# Elec_2013_Combined.net
KiCad netlist of a schematic drawn in EAGLE
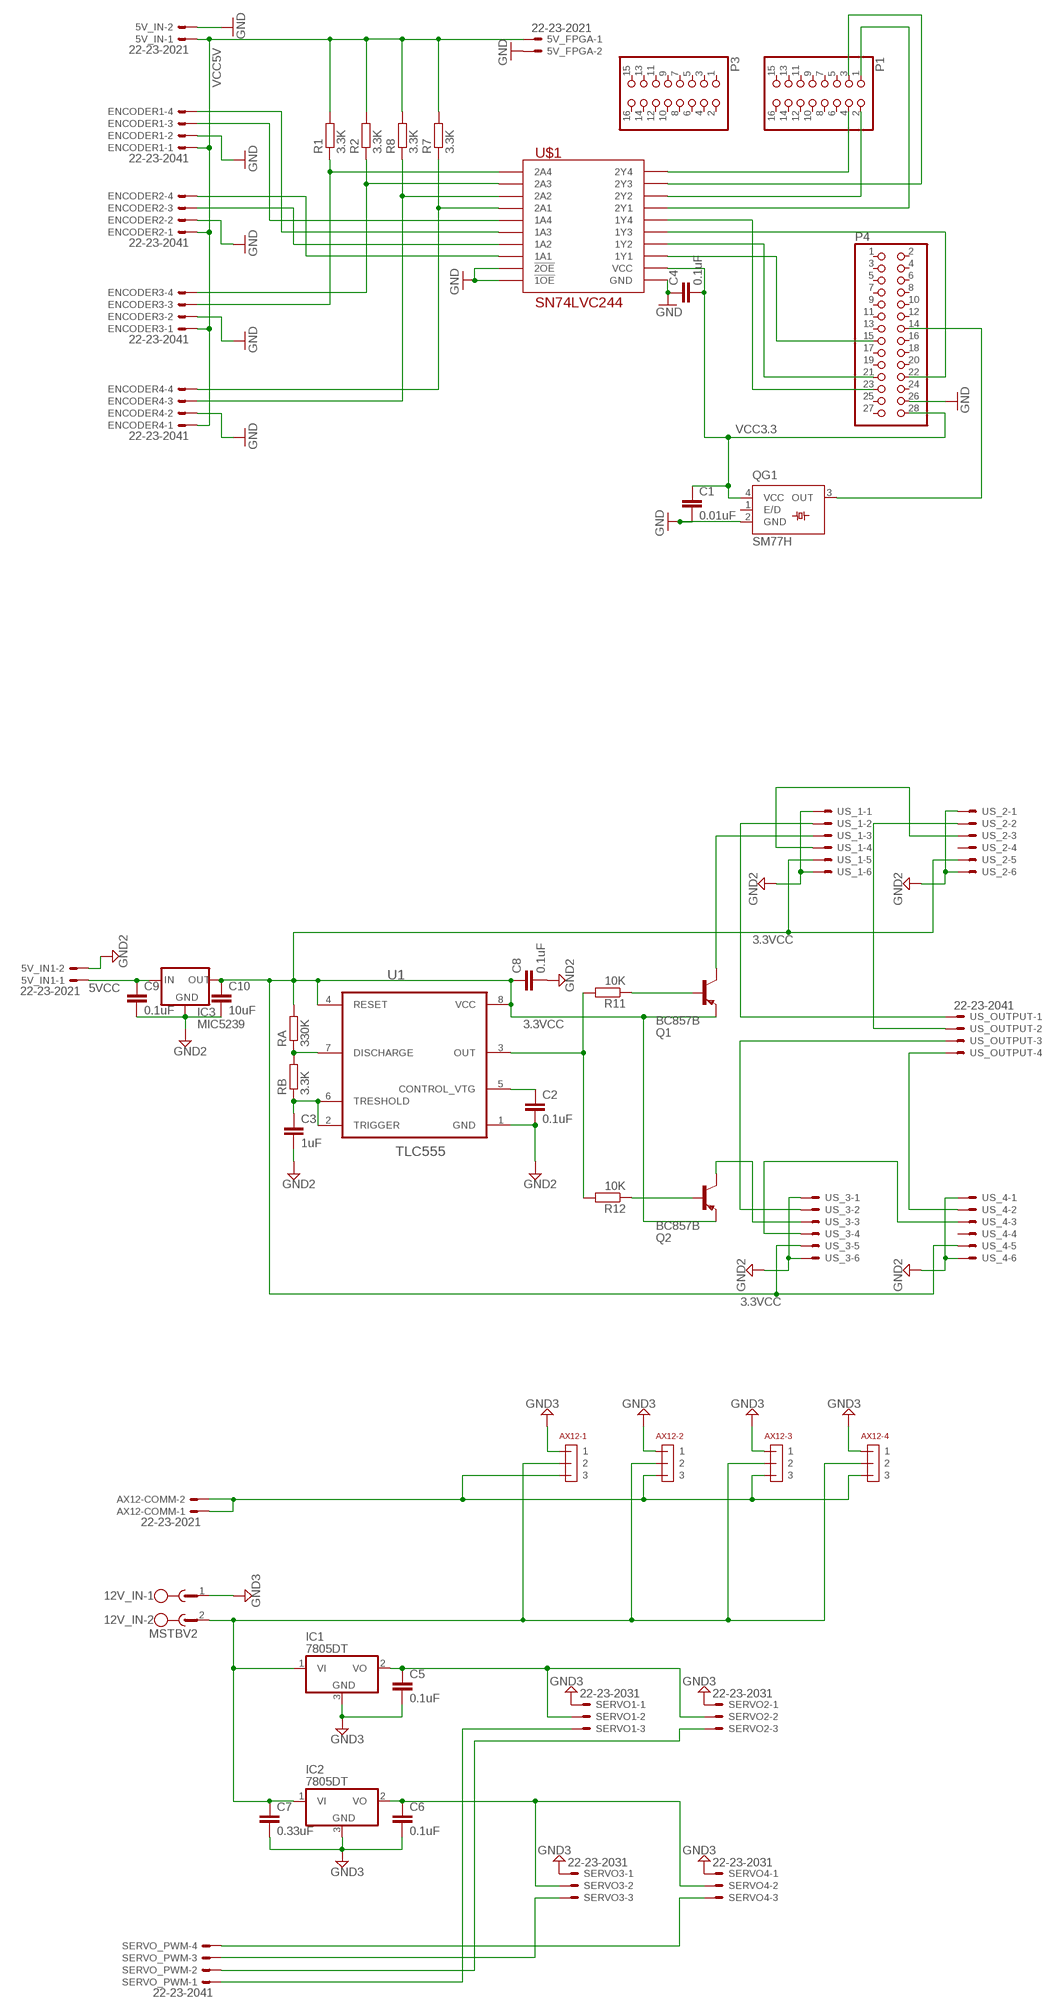
[diagram p0: schematic, sheet 1, part 1 of 2]
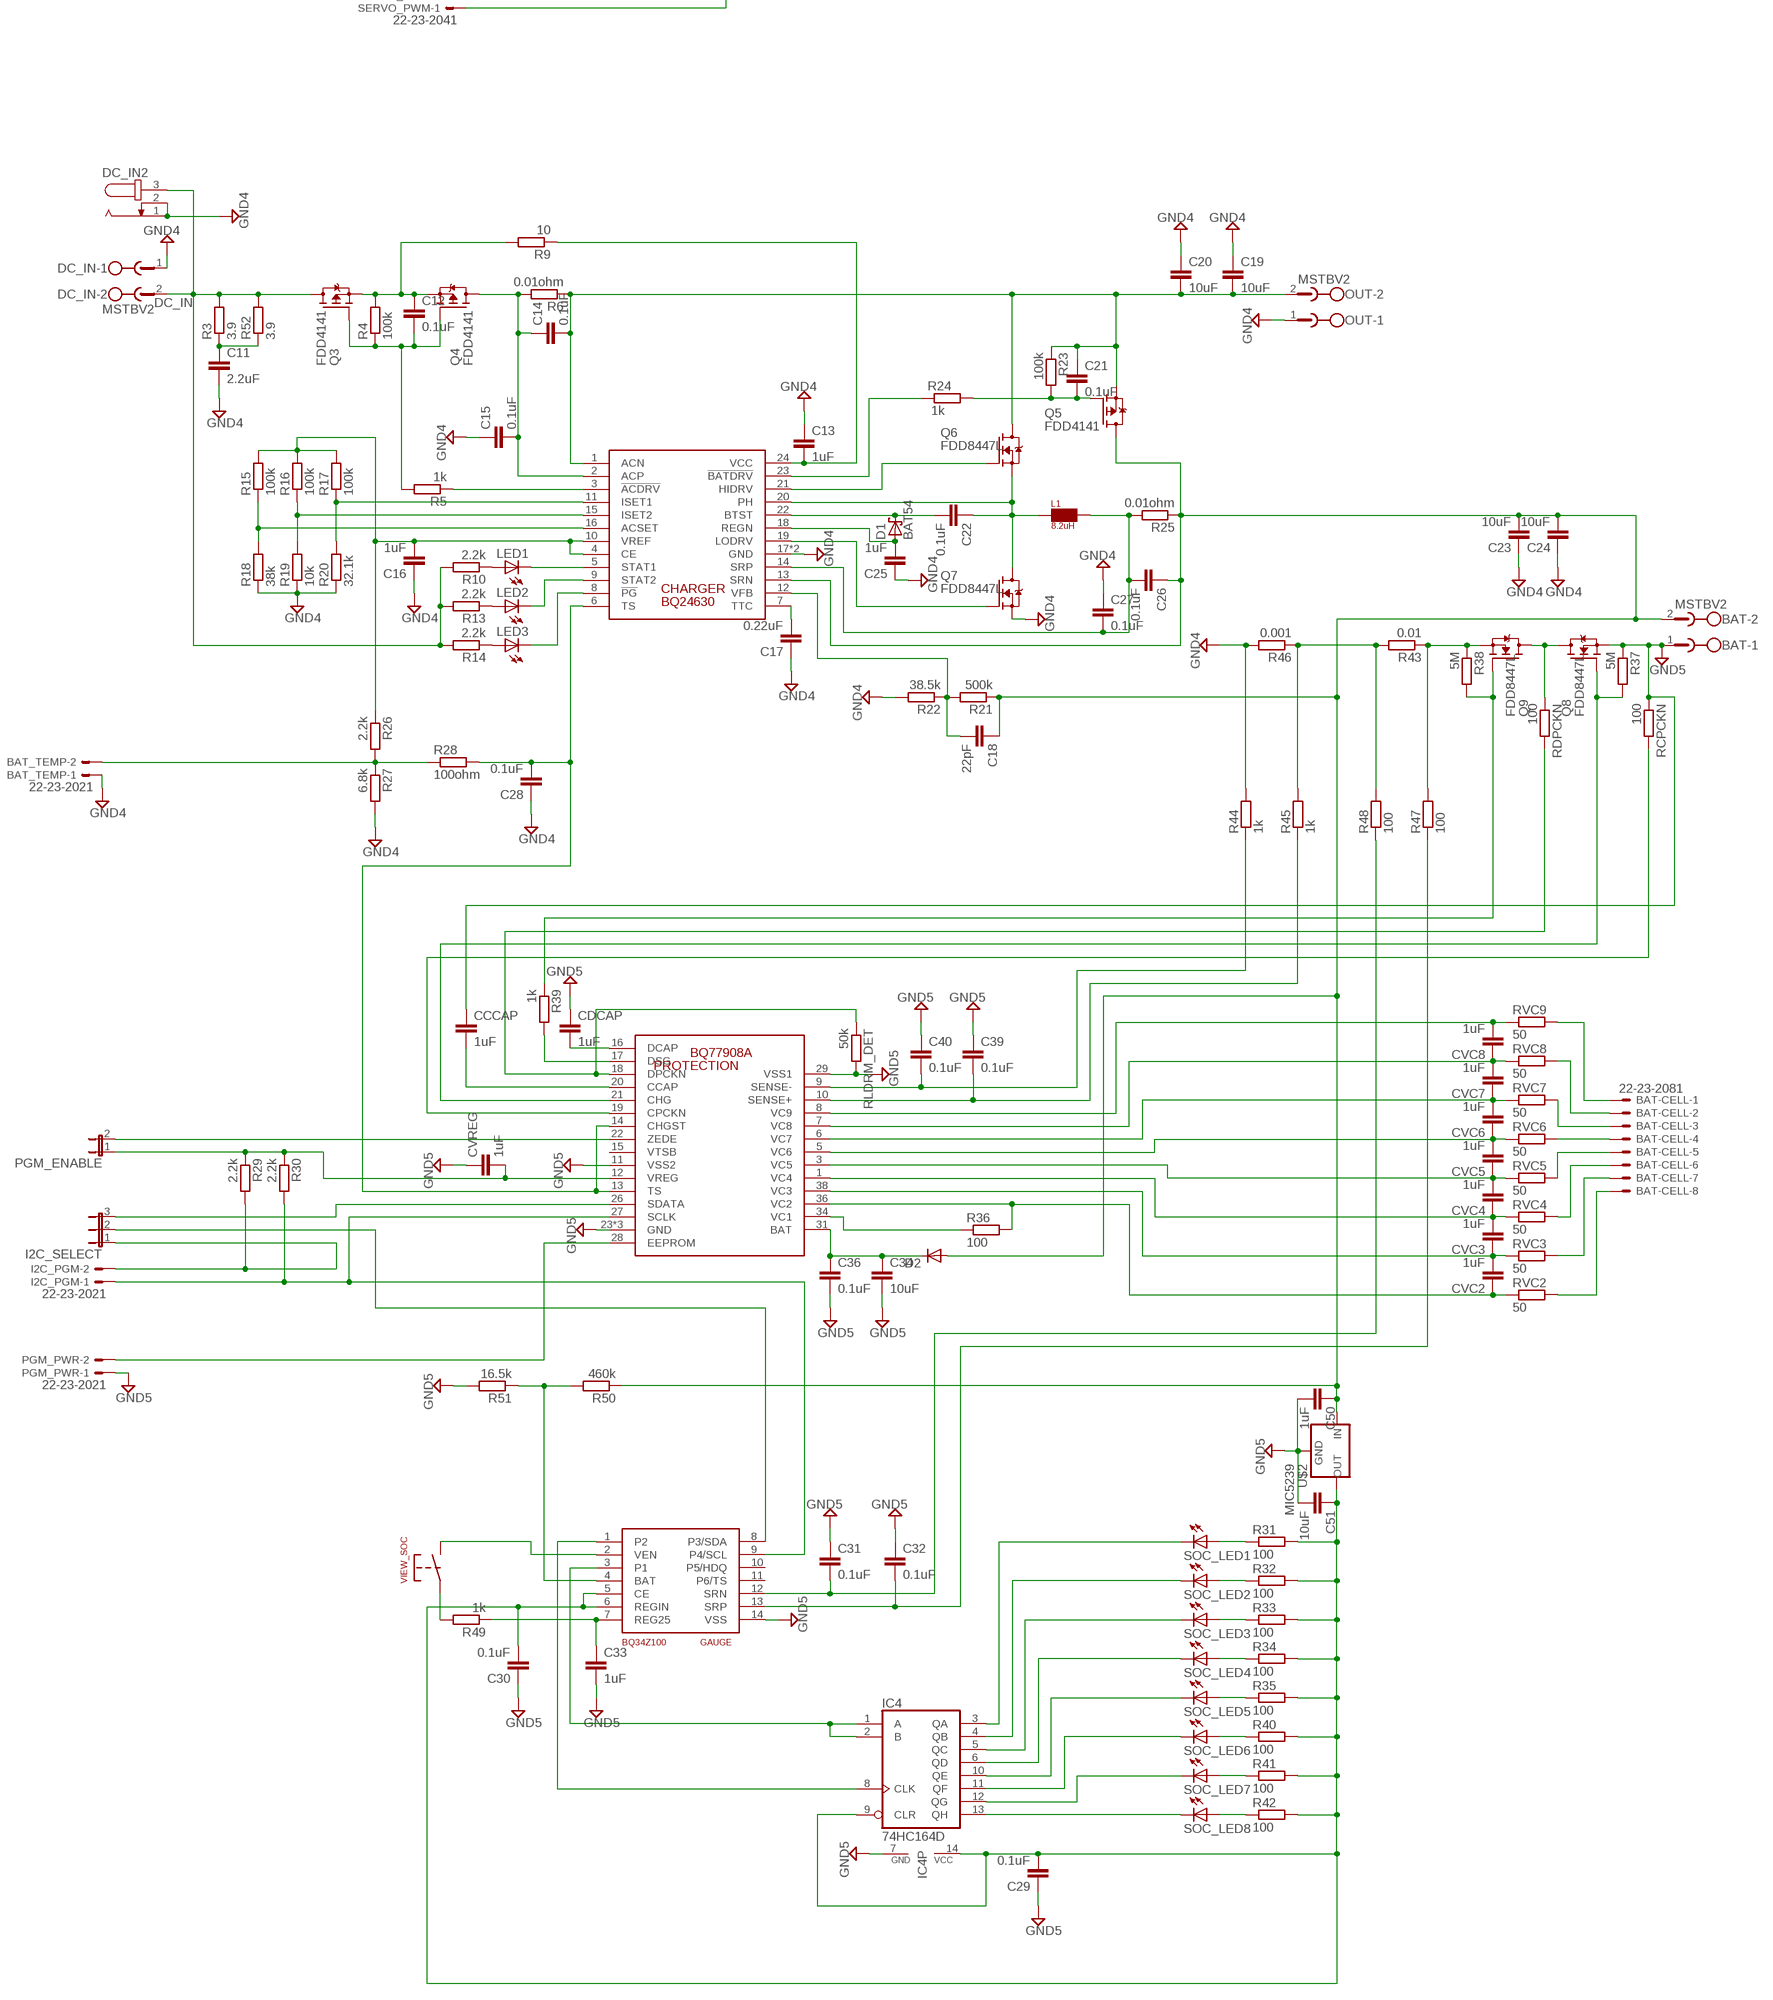
[diagram p1: schematic, sheet 1, part 2 of 2]

(export (version "E")
  (design (tool "Eeschema 10.0.6"))
  (components
    (comp (ref "5V_FPGA")
      (value "22-23-2021")
      (footprint "eagle-import:22-23-2021")
      (fields
        (field (name "MF") "MOLEX")
        (field (name "MF_1") "MOLEX")
        (field (name "MPN") "22-23-2021")
        (field (name "OC_FARNELL") "1462926")
        (field (name "OC_NEWARK") "25C3832")
      )
      (libsource (lib "eagle-import") (part "22-23-2021"))
    )
    (comp (ref "5V_IN")
      (value "22-23-2021")
      (footprint "eagle-import:22-23-2021")
      (fields (field (name "MF") "MOLEX"))
      (libsource (lib "eagle-import") (part "22-23-2021"))
    )
    (comp (ref "5V_IN1")
      (value "22-23-2021")
      (footprint "eagle-import:22-23-2021")
      (fields
        (field (name "MF") "MOLEX")
        (field (name "MF_1") "MOLEX")
        (field (name "MPN") "22-23-2021")
        (field (name "OC_FARNELL") "1462926")
        (field (name "OC_NEWARK") "25C3832")
      )
      (libsource (lib "eagle-import") (part "22-23-2021"))
    )
    (comp (ref "12V_IN")
      (value "MSTBV2")
      (footprint "eagle-import:MSTBV2")
      (fields (field (name "MPN") "MSTBV 2,5/2-GF-5.08"))
      (libsource (lib "eagle-import") (part "MSTBV2"))
    )
    (comp (ref "AX12-1")
      (value "22-03-5035")
      (footprint "eagle-import:22-03-5035")
      (libsource (lib "eagle-import") (part "22-03-5035"))
    )
    (comp (ref "AX12-2")
      (value "22-03-5035")
      (footprint "eagle-import:22-03-5035")
      (libsource (lib "eagle-import") (part "22-03-5035"))
    )
    (comp (ref "AX12-3")
      (value "22-03-5035")
      (footprint "eagle-import:22-03-5035")
      (libsource (lib "eagle-import") (part "22-03-5035"))
    )
    (comp (ref "AX12-4")
      (value "22-03-5035")
      (footprint "eagle-import:22-03-5035")
      (libsource (lib "eagle-import") (part "22-03-5035"))
    )
    (comp (ref "AX12-COMM")
      (value "22-23-2021")
      (footprint "eagle-import:22-23-2021")
      (fields (field (name "MF") "MOLEX"))
      (libsource (lib "eagle-import") (part "22-23-2021"))
    )
    (comp (ref "BAT")
      (value "MSTBV2")
      (footprint "eagle-import:MSTBV2")
      (fields
        (field (name "MPN") "MSTBV 2,5/2-GF-5.08")
        (field (name "MPN_1") "MSTBV 2,5/2-GF-5.08")
        (field (name "OC_FARNELL") "1792792")
        (field (name "OC_NEWARK") "69R9845")
      )
      (libsource (lib "eagle-import") (part "MSTBV2"))
    )
    (comp (ref "BAT-CELL")
      (value "22-23-2081")
      (footprint "eagle-import:22-23-2081")
      (fields (field (name "MF") "MOLEX"))
      (libsource (lib "eagle-import") (part "22-23-2081"))
    )
    (comp (ref "BAT_TEMP")
      (value "22-23-2021")
      (footprint "eagle-import:22-23-2021")
      (fields
        (field (name "MF") "MOLEX")
        (field (name "MF_1") "MOLEX")
        (field (name "MPN") "22-23-2021")
        (field (name "OC_FARNELL") "1462926")
        (field (name "OC_NEWARK") "25C3832")
      )
      (libsource (lib "eagle-import") (part "22-23-2021"))
    )
    (comp (ref "C1")
      (value "0.01uF")
      (footprint "eagle-import:C0603")
      (libsource (lib "eagle-import") (part "C-EUC0603"))
    )
    (comp (ref "C2")
      (value "0.1uF")
      (footprint "eagle-import:C0603")
      (libsource (lib "eagle-import") (part "C-EUC0603"))
    )
    (comp (ref "C3")
      (value "1uF")
      (footprint "eagle-import:C0603")
      (libsource (lib "eagle-import") (part "C-EUC0603"))
    )
    (comp (ref "C4")
      (value "0.1uF")
      (footprint "eagle-import:C0603")
      (libsource (lib "eagle-import") (part "C-EUC0603"))
    )
    (comp (ref "C5")
      (value "0.1uF")
      (footprint "eagle-import:C0603")
      (libsource (lib "eagle-import") (part "C-EUC0603"))
    )
    (comp (ref "C6")
      (value "0.1uF")
      (footprint "eagle-import:C0603")
      (libsource (lib "eagle-import") (part "C-EUC0603"))
    )
    (comp (ref "C7")
      (value "0.33uF")
      (footprint "eagle-import:C0603")
      (libsource (lib "eagle-import") (part "C-EUC0603"))
    )
    (comp (ref "C8")
      (value "0.1uF")
      (footprint "eagle-import:C0603")
      (libsource (lib "eagle-import") (part "C-EUC0603"))
    )
    (comp (ref "C9")
      (value "0.1uF")
      (footprint "eagle-import:C0603")
      (libsource (lib "eagle-import") (part "C-EUC0603"))
    )
    (comp (ref "C10")
      (value "10uF")
      (footprint "eagle-import:C0603")
      (libsource (lib "eagle-import") (part "C-EUC0603"))
    )
    (comp (ref "C11")
      (value "2.2uF")
      (footprint "eagle-import:C1206")
      (libsource (lib "eagle-import") (part "C-EUC1206"))
    )
    (comp (ref "C12")
      (value "0.1uF")
      (footprint "eagle-import:C0603")
      (libsource (lib "eagle-import") (part "C-EUC0603"))
    )
    (comp (ref "C13")
      (value "1uF")
      (footprint "eagle-import:C1206")
      (libsource (lib "eagle-import") (part "C-EUC1206"))
    )
    (comp (ref "C14")
      (value "0.1uF")
      (footprint "eagle-import:C0603")
      (libsource (lib "eagle-import") (part "C-EUC0603"))
    )
    (comp (ref "C15")
      (value "0.1uF")
      (footprint "eagle-import:C0603")
      (libsource (lib "eagle-import") (part "C-EUC0603"))
    )
    (comp (ref "C16")
      (value "1uF")
      (footprint "eagle-import:C0805")
      (libsource (lib "eagle-import") (part "C-EUC0805"))
    )
    (comp (ref "C17")
      (value "0.22uF")
      (footprint "eagle-import:C0603")
      (libsource (lib "eagle-import") (part "C-EUC0603"))
    )
    (comp (ref "C18")
      (value "22pF")
      (footprint "eagle-import:C0603")
      (libsource (lib "eagle-import") (part "C-EUC0603"))
    )
    (comp (ref "C19")
      (value "10uF")
      (footprint "eagle-import:C1812")
      (libsource (lib "eagle-import") (part "C-EUC1812"))
    )
    (comp (ref "C20")
      (value "10uF")
      (footprint "eagle-import:C1812")
      (libsource (lib "eagle-import") (part "C-EUC1812"))
    )
    (comp (ref "C21")
      (value "0.1uF")
      (footprint "eagle-import:C0603")
      (libsource (lib "eagle-import") (part "C-EUC0603"))
    )
    (comp (ref "C22")
      (value "0.1uF")
      (footprint "eagle-import:C0603")
      (libsource (lib "eagle-import") (part "C-EUC0603"))
    )
    (comp (ref "C23")
      (value "10uF")
      (footprint "eagle-import:C1812")
      (libsource (lib "eagle-import") (part "C-EUC1812"))
    )
    (comp (ref "C24")
      (value "10uF")
      (footprint "eagle-import:C1812")
      (libsource (lib "eagle-import") (part "C-EUC1812"))
    )
    (comp (ref "C25")
      (value "1uF")
      (footprint "eagle-import:C0805")
      (libsource (lib "eagle-import") (part "C-EUC0805"))
    )
    (comp (ref "C26")
      (value "0.1uF")
      (footprint "eagle-import:C0603")
      (libsource (lib "eagle-import") (part "C-EUC0603"))
    )
    (comp (ref "C27")
      (value "0.1uF")
      (footprint "eagle-import:C0603")
      (libsource (lib "eagle-import") (part "C-EUC0603"))
    )
    (comp (ref "C28")
      (value "0.1uF")
      (footprint "eagle-import:C0603")
      (libsource (lib "eagle-import") (part "C-EUC0603"))
    )
    (comp (ref "C29")
      (value "0.1uF")
      (footprint "eagle-import:C0603")
      (libsource (lib "eagle-import") (part "C-EUC0603"))
    )
    (comp (ref "C30")
      (value "0.1uF")
      (footprint "eagle-import:C0603")
      (libsource (lib "eagle-import") (part "C-EUC0603"))
    )
    (comp (ref "C31")
      (value "0.1uF")
      (footprint "eagle-import:C0603")
      (libsource (lib "eagle-import") (part "C-EUC0603"))
    )
    (comp (ref "C32")
      (value "0.1uF")
      (footprint "eagle-import:C0603")
      (libsource (lib "eagle-import") (part "C-EUC0603"))
    )
    (comp (ref "C33")
      (value "1uF")
      (footprint "eagle-import:C0603")
      (libsource (lib "eagle-import") (part "C-EUC0603"))
    )
    (comp (ref "C34")
      (value "10uF")
      (footprint "eagle-import:C1210")
      (libsource (lib "eagle-import") (part "C-EUC1210"))
    )
    (comp (ref "C36")
      (value "0.1uF")
      (footprint "eagle-import:C1210")
      (libsource (lib "eagle-import") (part "C-EUC1210"))
    )
    (comp (ref "C39")
      (value "0.1uF")
      (footprint "eagle-import:C0603")
      (libsource (lib "eagle-import") (part "C-EUC0603"))
    )
    (comp (ref "C40")
      (value "0.1uF")
      (footprint "eagle-import:C0603")
      (libsource (lib "eagle-import") (part "C-EUC0603"))
    )
    (comp (ref "C50")
      (value "1uF")
      (footprint "eagle-import:C0603")
      (libsource (lib "eagle-import") (part "C-EUC0603"))
    )
    (comp (ref "C51")
      (value "10uF")
      (footprint "eagle-import:C0603")
      (libsource (lib "eagle-import") (part "C-EUC0603"))
    )
    (comp (ref "CCCAP")
      (value "1uF")
      (footprint "eagle-import:C1206")
      (libsource (lib "eagle-import") (part "C-EUC1206"))
    )
    (comp (ref "CDCAP")
      (value "1uF")
      (footprint "eagle-import:C1206")
      (libsource (lib "eagle-import") (part "C-EUC1206"))
    )
    (comp (ref "CHARGER")
      (value "BQ24630")
      (footprint "eagle-import:QFN-24")
      (libsource (lib "eagle-import") (part "BQ24630"))
    )
    (comp (ref "CVC2")
      (value "1uF")
      (footprint "eagle-import:C0603")
      (libsource (lib "eagle-import") (part "C-EUC0603"))
    )
    (comp (ref "CVC3")
      (value "1uF")
      (footprint "eagle-import:C0603")
      (libsource (lib "eagle-import") (part "C-EUC0603"))
    )
    (comp (ref "CVC4")
      (value "1uF")
      (footprint "eagle-import:C0603")
      (libsource (lib "eagle-import") (part "C-EUC0603"))
    )
    (comp (ref "CVC5")
      (value "1uF")
      (footprint "eagle-import:C0603")
      (libsource (lib "eagle-import") (part "C-EUC0603"))
    )
    (comp (ref "CVC6")
      (value "1uF")
      (footprint "eagle-import:C0603")
      (libsource (lib "eagle-import") (part "C-EUC0603"))
    )
    (comp (ref "CVC7")
      (value "1uF")
      (footprint "eagle-import:C0603")
      (libsource (lib "eagle-import") (part "C-EUC0603"))
    )
    (comp (ref "CVC8")
      (value "1uF")
      (footprint "eagle-import:C0603")
      (libsource (lib "eagle-import") (part "C-EUC0603"))
    )
    (comp (ref "CVREG")
      (value "1uF")
      (footprint "eagle-import:C0603")
      (libsource (lib "eagle-import") (part "C-EUC0603"))
    )
    (comp (ref "D1")
      (value "BAT54")
      (footprint "eagle-import:SOT23")
      (libsource (lib "eagle-import") (part "BAT54"))
    )
    (comp (ref "D2")
      (value "DIODE-SOD123")
      (footprint "eagle-import:SOD123")
      (libsource (lib "eagle-import") (part "DIODE-SOD123"))
    )
    (comp (ref "DC_IN")
      (value "MSTBV2")
      (footprint "eagle-import:MSTBV2")
      (fields (field (name "MPN") "MSTBV 2,5/2-GF-5.08"))
      (libsource (lib "eagle-import") (part "MSTBV2"))
    )
    (comp (ref "DC_IN2")
      (value "JACK-PLUG1")
      (footprint "eagle-import:SPC4078")
      (libsource (lib "eagle-import") (part "JACK-PLUG1"))
    )
    (comp (ref "ENCODER1")
      (value "22-23-2041")
      (footprint "eagle-import:22-23-2041")
      (fields (field (name "MF") "MOLEX"))
      (libsource (lib "eagle-import") (part "22-23-2041"))
    )
    (comp (ref "ENCODER2")
      (value "22-23-2041")
      (footprint "eagle-import:22-23-2041")
      (fields (field (name "MF") "MOLEX"))
      (libsource (lib "eagle-import") (part "22-23-2041"))
    )
    (comp (ref "ENCODER3")
      (value "22-23-2041")
      (footprint "eagle-import:22-23-2041")
      (fields (field (name "MF") "MOLEX"))
      (libsource (lib "eagle-import") (part "22-23-2041"))
    )
    (comp (ref "ENCODER4")
      (value "22-23-2041")
      (footprint "eagle-import:22-23-2041")
      (fields (field (name "MF") "MOLEX"))
      (libsource (lib "eagle-import") (part "22-23-2041"))
    )
    (comp (ref "GAUGE")
      (value "BQ34Z100")
      (footprint "eagle-import:TSSOP-14-0.65MM")
      (libsource (lib "eagle-import") (part "BQ34Z100"))
    )
    (comp (ref "I2C_PGM")
      (value "22-23-2021")
      (footprint "eagle-import:22-23-2021")
      (fields
        (field (name "MF") "MOLEX")
        (field (name "MF_1") "MOLEX")
        (field (name "MPN") "22-23-2021")
        (field (name "OC_FARNELL") "1462926")
        (field (name "OC_NEWARK") "25C3832")
      )
      (libsource (lib "eagle-import") (part "22-23-2021"))
    )
    (comp (ref "I2C_SELECT")
      (value "JP2E")
      (footprint "eagle-import:JP2")
      (libsource (lib "eagle-import") (part "JP2E"))
    )
    (comp (ref "IC1")
      (value "7805DT")
      (footprint "eagle-import:TO252")
      (libsource (lib "eagle-import") (part "78DT05"))
    )
    (comp (ref "IC2")
      (value "7805DT")
      (footprint "eagle-import:TO252")
      (libsource (lib "eagle-import") (part "78DT05"))
    )
    (comp (ref "IC3")
      (value "MIC5239")
      (footprint "eagle-import:SOT223")
      (libsource (lib "eagle-import") (part "MIC5239"))
    )
    (comp (ref "IC4")
      (value "74HC164D")
      (footprint "eagle-import:SO14")
      (libsource (lib "eagle-import") (part "74164DHC"))
    )
    (comp (ref "L1")
      (value "8.2uH")
      (footprint "eagle-import:5050CE")
      (libsource (lib "eagle-import") (part "IHLP-5050CE"))
    )
    (comp (ref "LED1")
      (value "LEDCHIP-LED0603")
      (footprint "eagle-import:CHIP-LED0603")
      (libsource (lib "eagle-import") (part "LEDCHIP-LED0603"))
    )
    (comp (ref "LED2")
      (value "LEDCHIP-LED0603")
      (footprint "eagle-import:CHIP-LED0603")
      (libsource (lib "eagle-import") (part "LEDCHIP-LED0603"))
    )
    (comp (ref "LED3")
      (value "LEDCHIP-LED0603")
      (footprint "eagle-import:CHIP-LED0603")
      (libsource (lib "eagle-import") (part "LEDCHIP-LED0603"))
    )
    (comp (ref "OUT")
      (value "MSTBV2")
      (footprint "eagle-import:MSTBV2")
      (fields
        (field (name "MPN") "MSTBV 2,5/2-GF-5.08")
        (field (name "MPN_1") "MSTBV 2,5/2-GF-5.08")
        (field (name "OC_FARNELL") "1792792")
        (field (name "OC_NEWARK") "69R9845")
      )
      (libsource (lib "eagle-import") (part "MSTBV2"))
    )
    (comp (ref "P1")
      (value "PINHD-2X8")
      (footprint "eagle-import:2X08")
      (libsource (lib "eagle-import") (part "PINHD-2X8"))
    )
    (comp (ref "P3")
      (value "PINHD-2X8")
      (footprint "eagle-import:2X08")
      (libsource (lib "eagle-import") (part "PINHD-2X8"))
    )
    (comp (ref "P4")
      (value "PINHD-2X14")
      (footprint "eagle-import:2X14")
      (libsource (lib "eagle-import") (part "PINHD-2X14"))
    )
    (comp (ref "PGM_ENABLE")
      (value "JP1E")
      (footprint "eagle-import:JP1")
      (libsource (lib "eagle-import") (part "JP1E"))
    )
    (comp (ref "PGM_PWR")
      (value "22-23-2021")
      (footprint "eagle-import:22-23-2021")
      (fields
        (field (name "MF") "MOLEX")
        (field (name "MF_1") "MOLEX")
        (field (name "MPN") "22-23-2021")
        (field (name "OC_FARNELL") "1462926")
        (field (name "OC_NEWARK") "25C3832")
      )
      (libsource (lib "eagle-import") (part "22-23-2021"))
    )
    (comp (ref "PROTECTION")
      (value "BQ77908A")
      (footprint "eagle-import:TSSOP-38-0.5MM")
      (libsource (lib "eagle-import") (part "BQ77908A"))
    )
    (comp (ref "Q1")
      (value "BC857B")
      (footprint "eagle-import:SOT23")
      (libsource (lib "eagle-import") (part "-?SOT23MMBTA56"))
    )
    (comp (ref "Q2")
      (value "BC857B")
      (footprint "eagle-import:SOT23")
      (libsource (lib "eagle-import") (part "-?SOT23MMBTA56"))
    )
    (comp (ref "Q3")
      (value "FDD4141")
      (footprint "eagle-import:TO252")
      (libsource (lib "eagle-import") (part "FDD4141TO252"))
    )
    (comp (ref "Q4")
      (value "FDD4141")
      (footprint "eagle-import:TO252")
      (libsource (lib "eagle-import") (part "FDD4141TO252"))
    )
    (comp (ref "Q5")
      (value "FDD4141")
      (footprint "eagle-import:TO252")
      (libsource (lib "eagle-import") (part "FDD4141TO252"))
    )
    (comp (ref "Q6")
      (value "FDD8447L")
      (footprint "eagle-import:TO252")
      (libsource (lib "eagle-import") (part "FDD8447L"))
    )
    (comp (ref "Q7")
      (value "FDD8447L")
      (footprint "eagle-import:TO252")
      (libsource (lib "eagle-import") (part "FDD8447L"))
    )
    (comp (ref "Q8")
      (value "FDD8447L")
      (footprint "eagle-import:TO252")
      (libsource (lib "eagle-import") (part "FDD8447L"))
    )
    (comp (ref "Q9")
      (value "FDD8447L")
      (footprint "eagle-import:TO252")
      (libsource (lib "eagle-import") (part "FDD8447L"))
    )
    (comp (ref "QG1")
      (value "SM77H")
      (footprint "eagle-import:SM77H")
      (libsource (lib "eagle-import") (part "SM77H"))
    )
    (comp (ref "R1")
      (value "3.3K")
      (footprint "eagle-import:R0603")
      (libsource (lib "eagle-import") (part "R-EU_R0603"))
    )
    (comp (ref "R2")
      (value "3.3K")
      (footprint "eagle-import:R0603")
      (libsource (lib "eagle-import") (part "R-EU_R0603"))
    )
    (comp (ref "R3")
      (value "3.9")
      (footprint "eagle-import:R1206")
      (libsource (lib "eagle-import") (part "R-EU_R1206"))
    )
    (comp (ref "R4")
      (value "100k")
      (footprint "eagle-import:R0603")
      (libsource (lib "eagle-import") (part "R-EU_R0603"))
    )
    (comp (ref "R5")
      (value "1k")
      (footprint "eagle-import:R0603")
      (libsource (lib "eagle-import") (part "R-EU_R0603"))
    )
    (comp (ref "R6")
      (value "0.01ohm")
      (footprint "eagle-import:R2010")
      (libsource (lib "eagle-import") (part "R-EU_R2010"))
    )
    (comp (ref "R7")
      (value "3.3K")
      (footprint "eagle-import:R0603")
      (libsource (lib "eagle-import") (part "R-EU_R0603"))
    )
    (comp (ref "R8")
      (value "3.3K")
      (footprint "eagle-import:R0603")
      (libsource (lib "eagle-import") (part "R-EU_R0603"))
    )
    (comp (ref "R9")
      (value "10")
      (footprint "eagle-import:R1206")
      (libsource (lib "eagle-import") (part "R-EU_R1206"))
    )
    (comp (ref "R10")
      (value "2.2k")
      (footprint "eagle-import:R0603")
      (libsource (lib "eagle-import") (part "R-EU_R0603"))
    )
    (comp (ref "R11")
      (value "10K")
      (footprint "eagle-import:R0603")
      (libsource (lib "eagle-import") (part "R-EU_R0603"))
    )
    (comp (ref "R12")
      (value "10K")
      (footprint "eagle-import:R0603")
      (libsource (lib "eagle-import") (part "R-EU_R0603"))
    )
    (comp (ref "R13")
      (value "2.2k")
      (footprint "eagle-import:R0603")
      (libsource (lib "eagle-import") (part "R-EU_R0603"))
    )
    (comp (ref "R14")
      (value "2.2k")
      (footprint "eagle-import:R0603")
      (libsource (lib "eagle-import") (part "R-EU_R0603"))
    )
    (comp (ref "R15")
      (value "100k")
      (footprint "eagle-import:R0805")
      (libsource (lib "eagle-import") (part "R-EU_R0805"))
    )
    (comp (ref "R16")
      (value "100k")
      (footprint "eagle-import:R0805")
      (libsource (lib "eagle-import") (part "R-EU_R0805"))
    )
    (comp (ref "R17")
      (value "100k")
      (footprint "eagle-import:R0805")
      (libsource (lib "eagle-import") (part "R-EU_R0805"))
    )
    (comp (ref "R18")
      (value "38k")
      (footprint "eagle-import:R0805")
      (libsource (lib "eagle-import") (part "R-EU_R0805"))
    )
    (comp (ref "R19")
      (value "10k")
      (footprint "eagle-import:R0805")
      (libsource (lib "eagle-import") (part "R-EU_R0805"))
    )
    (comp (ref "R20")
      (value "32.1k")
      (footprint "eagle-import:R0805")
      (libsource (lib "eagle-import") (part "R-EU_R0805"))
    )
    (comp (ref "R21")
      (value "500k")
      (footprint "eagle-import:R0805")
      (libsource (lib "eagle-import") (part "R-EU_R0805"))
    )
    (comp (ref "R22")
      (value "38.5k")
      (footprint "eagle-import:R0805")
      (libsource (lib "eagle-import") (part "R-EU_R0805"))
    )
    (comp (ref "R23")
      (value "100k")
      (footprint "eagle-import:R0603")
      (libsource (lib "eagle-import") (part "R-EU_R0603"))
    )
    (comp (ref "R24")
      (value "1k")
      (footprint "eagle-import:R0603")
      (libsource (lib "eagle-import") (part "R-EU_R0603"))
    )
    (comp (ref "R25")
      (value "0.01ohm")
      (footprint "eagle-import:R2010")
      (libsource (lib "eagle-import") (part "R-EU_R2010"))
    )
    (comp (ref "R26")
      (value "2.2k")
      (footprint "eagle-import:R0603")
      (libsource (lib "eagle-import") (part "R-EU_R0603"))
    )
    (comp (ref "R27")
      (value "6.8k")
      (footprint "eagle-import:R0603")
      (libsource (lib "eagle-import") (part "R-EU_R0603"))
    )
    (comp (ref "R28")
      (value "100ohm")
      (footprint "eagle-import:R0603")
      (libsource (lib "eagle-import") (part "R-EU_R0603"))
    )
    (comp (ref "R29")
      (value "2.2k")
      (footprint "eagle-import:R0603")
      (libsource (lib "eagle-import") (part "R-EU_R0603"))
    )
    (comp (ref "R30")
      (value "2.2k")
      (footprint "eagle-import:R0603")
      (libsource (lib "eagle-import") (part "R-EU_R0603"))
    )
    (comp (ref "R31")
      (value "100")
      (footprint "eagle-import:R0603")
      (libsource (lib "eagle-import") (part "R-EU_R0603"))
    )
    (comp (ref "R32")
      (value "100")
      (footprint "eagle-import:R0603")
      (libsource (lib "eagle-import") (part "R-EU_R0603"))
    )
    (comp (ref "R33")
      (value "100")
      (footprint "eagle-import:R0603")
      (libsource (lib "eagle-import") (part "R-EU_R0603"))
    )
    (comp (ref "R34")
      (value "100")
      (footprint "eagle-import:R0603")
      (libsource (lib "eagle-import") (part "R-EU_R0603"))
    )
    (comp (ref "R35")
      (value "100")
      (footprint "eagle-import:R0603")
      (libsource (lib "eagle-import") (part "R-EU_R0603"))
    )
    (comp (ref "R36")
      (value "100")
      (footprint "eagle-import:R0603")
      (libsource (lib "eagle-import") (part "R-EU_R0603"))
    )
    (comp (ref "R37")
      (value "5M")
      (footprint "eagle-import:R0603")
      (libsource (lib "eagle-import") (part "R-EU_R0603"))
    )
    (comp (ref "R38")
      (value "5M")
      (footprint "eagle-import:R0603")
      (libsource (lib "eagle-import") (part "R-EU_R0603"))
    )
    (comp (ref "R39")
      (value "1k")
      (footprint "eagle-import:R0603")
      (libsource (lib "eagle-import") (part "R-EU_R0603"))
    )
    (comp (ref "R40")
      (value "100")
      (footprint "eagle-import:R0603")
      (libsource (lib "eagle-import") (part "R-EU_R0603"))
    )
    (comp (ref "R41")
      (value "100")
      (footprint "eagle-import:R0603")
      (libsource (lib "eagle-import") (part "R-EU_R0603"))
    )
    (comp (ref "R42")
      (value "100")
      (footprint "eagle-import:R0603")
      (libsource (lib "eagle-import") (part "R-EU_R0603"))
    )
    (comp (ref "R43")
      (value "0.01")
      (footprint "eagle-import:R2010")
      (libsource (lib "eagle-import") (part "R-EU_R2010"))
    )
    (comp (ref "R44")
      (value "1k")
      (footprint "eagle-import:R0603")
      (libsource (lib "eagle-import") (part "R-EU_R0603"))
    )
    (comp (ref "R45")
      (value "1k")
      (footprint "eagle-import:R0603")
      (libsource (lib "eagle-import") (part "R-EU_R0603"))
    )
    (comp (ref "R46")
      (value "0.001")
      (footprint "eagle-import:R2010")
      (libsource (lib "eagle-import") (part "R-EU_R2010"))
    )
    (comp (ref "R47")
      (value "100")
      (footprint "eagle-import:R0603")
      (libsource (lib "eagle-import") (part "R-EU_R0603"))
    )
    (comp (ref "R48")
      (value "100")
      (footprint "eagle-import:R0603")
      (libsource (lib "eagle-import") (part "R-EU_R0603"))
    )
    (comp (ref "R49")
      (value "1k")
      (footprint "eagle-import:R0603")
      (libsource (lib "eagle-import") (part "R-EU_R0603"))
    )
    (comp (ref "R50")
      (value "460k")
      (footprint "eagle-import:R0805")
      (libsource (lib "eagle-import") (part "R-EU_R0805"))
    )
    (comp (ref "R51")
      (value "16.5k")
      (footprint "eagle-import:R0603")
      (libsource (lib "eagle-import") (part "R-EU_R0603"))
    )
    (comp (ref "R52")
      (value "3.9")
      (footprint "eagle-import:R1206")
      (libsource (lib "eagle-import") (part "R-EU_R1206"))
    )
    (comp (ref "RA")
      (value "330K")
      (footprint "eagle-import:R0603")
      (libsource (lib "eagle-import") (part "R-EU_R0603"))
    )
    (comp (ref "RB")
      (value "3.3K")
      (footprint "eagle-import:R0603")
      (libsource (lib "eagle-import") (part "R-EU_R0603"))
    )
    (comp (ref "RCPCKN")
      (value "100")
      (footprint "eagle-import:R0603")
      (libsource (lib "eagle-import") (part "R-EU_R0603"))
    )
    (comp (ref "RDPCKN")
      (value "100")
      (footprint "eagle-import:R0603")
      (libsource (lib "eagle-import") (part "R-EU_R0603"))
    )
    (comp (ref "RLDRM_DET")
      (value "50k")
      (footprint "eagle-import:R0603")
      (libsource (lib "eagle-import") (part "R-EU_R0603"))
    )
    (comp (ref "RVC2")
      (value "50")
      (footprint "eagle-import:R1206")
      (libsource (lib "eagle-import") (part "R-EU_R1206"))
    )
    (comp (ref "RVC3")
      (value "50")
      (footprint "eagle-import:R1206")
      (libsource (lib "eagle-import") (part "R-EU_R1206"))
    )
    (comp (ref "RVC4")
      (value "50")
      (footprint "eagle-import:R1206")
      (libsource (lib "eagle-import") (part "R-EU_R1206"))
    )
    (comp (ref "RVC5")
      (value "50")
      (footprint "eagle-import:R1206")
      (libsource (lib "eagle-import") (part "R-EU_R1206"))
    )
    (comp (ref "RVC6")
      (value "50")
      (footprint "eagle-import:R1206")
      (libsource (lib "eagle-import") (part "R-EU_R1206"))
    )
    (comp (ref "RVC7")
      (value "50")
      (footprint "eagle-import:R1206")
      (libsource (lib "eagle-import") (part "R-EU_R1206"))
    )
    (comp (ref "RVC8")
      (value "50")
      (footprint "eagle-import:R1206")
      (libsource (lib "eagle-import") (part "R-EU_R1206"))
    )
    (comp (ref "RVC9")
      (value "50")
      (footprint "eagle-import:R1206")
      (libsource (lib "eagle-import") (part "R-EU_R1206"))
    )
    (comp (ref "SERVO1")
      (value "22-23-2031")
      (footprint "eagle-import:22-23-2031")
      (fields (field (name "MF") "MOLEX"))
      (libsource (lib "eagle-import") (part "22-23-2031"))
    )
    (comp (ref "SERVO2")
      (value "22-23-2031")
      (footprint "eagle-import:22-23-2031")
      (fields (field (name "MF") "MOLEX"))
      (libsource (lib "eagle-import") (part "22-23-2031"))
    )
    (comp (ref "SERVO3")
      (value "22-23-2031")
      (footprint "eagle-import:22-23-2031")
      (fields (field (name "MF") "MOLEX"))
      (libsource (lib "eagle-import") (part "22-23-2031"))
    )
    (comp (ref "SERVO4")
      (value "22-23-2031")
      (footprint "eagle-import:22-23-2031")
      (fields (field (name "MF") "MOLEX"))
      (libsource (lib "eagle-import") (part "22-23-2031"))
    )
    (comp (ref "SERVO_PWM")
      (value "22-23-2041")
      (footprint "eagle-import:22-23-2041")
      (fields (field (name "MF") "MOLEX"))
      (libsource (lib "eagle-import") (part "22-23-2041"))
    )
    (comp (ref "SOC_LED1")
      (value "LEDCHIP-LED0603")
      (footprint "eagle-import:CHIP-LED0603")
      (libsource (lib "eagle-import") (part "LEDCHIP-LED0603"))
    )
    (comp (ref "SOC_LED2")
      (value "LEDCHIP-LED0603")
      (footprint "eagle-import:CHIP-LED0603")
      (libsource (lib "eagle-import") (part "LEDCHIP-LED0603"))
    )
    (comp (ref "SOC_LED3")
      (value "LEDCHIP-LED0603")
      (footprint "eagle-import:CHIP-LED0603")
      (libsource (lib "eagle-import") (part "LEDCHIP-LED0603"))
    )
    (comp (ref "SOC_LED4")
      (value "LEDCHIP-LED0603")
      (footprint "eagle-import:CHIP-LED0603")
      (libsource (lib "eagle-import") (part "LEDCHIP-LED0603"))
    )
    (comp (ref "SOC_LED5")
      (value "LEDCHIP-LED0603")
      (footprint "eagle-import:CHIP-LED0603")
      (libsource (lib "eagle-import") (part "LEDCHIP-LED0603"))
    )
    (comp (ref "SOC_LED6")
      (value "LEDCHIP-LED0603")
      (footprint "eagle-import:CHIP-LED0603")
      (libsource (lib "eagle-import") (part "LEDCHIP-LED0603"))
    )
    (comp (ref "SOC_LED7")
      (value "LEDCHIP-LED0603")
      (footprint "eagle-import:CHIP-LED0603")
      (libsource (lib "eagle-import") (part "LEDCHIP-LED0603"))
    )
    (comp (ref "SOC_LED8")
      (value "LEDCHIP-LED0603")
      (footprint "eagle-import:CHIP-LED0603")
      (libsource (lib "eagle-import") (part "LEDCHIP-LED0603"))
    )
    (comp (ref "U$1")
      (value "SN74LVC244")
      (footprint "eagle-import:TSSOP-20-0.65MM")
      (libsource (lib "eagle-import") (part "SN74LVC244"))
    )
    (comp (ref "U$2")
      (value "MIC5239")
      (footprint "eagle-import:SOT223")
      (libsource (lib "eagle-import") (part "MIC5239"))
    )
    (comp (ref "U1")
      (value "TLC555")
      (footprint "eagle-import:SOIC127P600X175-8N")
      (fields (field (name "MPN") "LM555CM"))
      (libsource (lib "eagle-import") (part "LM555CM"))
    )
    (comp (ref "US_1")
      (value "22-23-2061")
      (footprint "eagle-import:22-23-2061")
      (fields (field (name "MF") "MOLEX"))
      (libsource (lib "eagle-import") (part "22-23-2061"))
    )
    (comp (ref "US_2")
      (value "22-23-2061")
      (footprint "eagle-import:22-23-2061")
      (fields (field (name "MF") "MOLEX"))
      (libsource (lib "eagle-import") (part "22-23-2061"))
    )
    (comp (ref "US_3")
      (value "22-23-2061")
      (footprint "eagle-import:22-23-2061")
      (fields (field (name "MF") "MOLEX"))
      (libsource (lib "eagle-import") (part "22-23-2061"))
    )
    (comp (ref "US_4")
      (value "22-23-2061")
      (footprint "eagle-import:22-23-2061")
      (fields (field (name "MF") "MOLEX"))
      (libsource (lib "eagle-import") (part "22-23-2061"))
    )
    (comp (ref "US_OUTPUT")
      (value "22-23-2041")
      (footprint "eagle-import:22-23-2041")
      (fields (field (name "MF") "MOLEX"))
      (libsource (lib "eagle-import") (part "22-23-2041"))
    )
    (comp (ref "VIEW_SOC")
      (value "PUSHBUTTON")
      (footprint "eagle-import:PUSHBUTTON")
      (libsource (lib "eagle-import") (part "PUSHBUTTON"))
    )
  )
  (nets
    (net (code "1") (name "/3.3VCC") (class "Default")
      (node (ref "C10") (pin "1") (pinfunction "1_1") (pintype "passive"))
      (node (ref "C8") (pin "1") (pinfunction "1_1") (pintype "passive"))
      (node (ref "IC3") (pin "3") (pinfunction "OUT_3") (pintype "passive"))
      (node (ref "Q1") (pin "2") (pinfunction "E_2") (pintype "passive"))
      (node (ref "Q2") (pin "2") (pinfunction "E_2") (pintype "passive"))
      (node (ref "RA") (pin "2") (pinfunction "2_2") (pintype "passive"))
      (node (ref "U1") (pin "4") (pinfunction "RESET_4") (pintype "input"))
      (node (ref "U1") (pin "8") (pinfunction "VCC_8") (pintype "power_in"))
      (node (ref "US_1") (pin "5") (pinfunction "S_5") (pintype "passive"))
      (node (ref "US_2") (pin "5") (pinfunction "S_5") (pintype "passive"))
      (node (ref "US_3") (pin "5") (pinfunction "S_5") (pintype "passive"))
      (node (ref "US_4") (pin "5") (pinfunction "S_5") (pintype "passive"))
    )
    (net (code "2") (name "/5VCC") (class "Default")
      (node (ref "5V_IN1") (pin "1") (pinfunction "S_1") (pintype "passive"))
      (node (ref "C9") (pin "1") (pinfunction "1_1") (pintype "passive"))
      (node (ref "IC3") (pin "1") (pinfunction "IN_1") (pintype "input"))
    )
    (net (code "3") (name "/DC_IN") (class "Default")
      (node (ref "DC_IN") (pin "2") (pinfunction "1_2") (pintype "passive"))
      (node (ref "DC_IN2") (pin "3") (pinfunction "3_3") (pintype "passive"))
      (node (ref "Q3") (pin "3") (pinfunction "D_3") (pintype "passive"))
      (node (ref "R10") (pin "2") (pinfunction "2_2") (pintype "passive"))
      (node (ref "R13") (pin "2") (pinfunction "2_2") (pintype "passive"))
      (node (ref "R14") (pin "2") (pinfunction "2_2") (pintype "passive"))
      (node (ref "R3") (pin "2") (pinfunction "2_2") (pintype "passive"))
      (node (ref "R52") (pin "2") (pinfunction "2_2") (pintype "passive"))
    )
    (net (code "4") (name "/VCC3.3") (class "Default")
      (node (ref "C1") (pin "1") (pinfunction "1_1") (pintype "passive"))
      (node (ref "C4") (pin "2") (pinfunction "2_2") (pintype "passive"))
      (node (ref "P4") (pin "28") (pinfunction "28_28") (pintype "passive"))
      (node (ref "QG1") (pin "4") (pinfunction "VCC_4") (pintype "power_in"))
      (node (ref "U$1") (pin "P$20") (pinfunction "VCC_P$20") (pintype "bidirectional"))
    )
    (net (code "5") (name "/VCC5V") (class "Default")
      (node (ref "5V_FPGA") (pin "1") (pinfunction "S_1") (pintype "passive"))
      (node (ref "5V_IN") (pin "1") (pinfunction "S_1") (pintype "passive"))
      (node (ref "ENCODER1") (pin "1") (pinfunction "S_1") (pintype "passive"))
      (node (ref "ENCODER2") (pin "1") (pinfunction "S_1") (pintype "passive"))
      (node (ref "ENCODER3") (pin "1") (pinfunction "S_1") (pintype "passive"))
      (node (ref "ENCODER4") (pin "1") (pinfunction "S_1") (pintype "passive"))
      (node (ref "R1") (pin "2") (pinfunction "2_2") (pintype "passive"))
      (node (ref "R2") (pin "2") (pinfunction "2_2") (pintype "passive"))
      (node (ref "R7") (pin "2") (pinfunction "2_2") (pintype "passive"))
      (node (ref "R8") (pin "2") (pinfunction "2_2") (pintype "passive"))
    )
    (net (code "6") (name "GND") (class "Default")
      (node (ref "5V_FPGA") (pin "2") (pinfunction "S_2") (pintype "passive"))
      (node (ref "5V_IN") (pin "2") (pinfunction "S_2") (pintype "passive"))
      (node (ref "C1") (pin "2") (pinfunction "2_2") (pintype "passive"))
      (node (ref "C4") (pin "1") (pinfunction "1_1") (pintype "passive"))
      (node (ref "ENCODER1") (pin "2") (pinfunction "S_2") (pintype "passive"))
      (node (ref "ENCODER2") (pin "2") (pinfunction "S_2") (pintype "passive"))
      (node (ref "ENCODER3") (pin "2") (pinfunction "S_2") (pintype "passive"))
      (node (ref "ENCODER4") (pin "2") (pinfunction "S_2") (pintype "passive"))
      (node (ref "P4") (pin "26") (pinfunction "26_26") (pintype "passive"))
      (node (ref "QG1") (pin "2") (pinfunction "GND_2") (pintype "power_in"))
      (node (ref "U$1") (pin "P$1") (pinfunction "~{1OE}_P$1") (pintype "bidirectional"))
      (node (ref "U$1") (pin "P$10") (pinfunction "GND_P$10") (pintype "bidirectional"))
      (node (ref "U$1") (pin "P$19") (pinfunction "~{2OE}_P$19") (pintype "bidirectional"))
    )
    (net (code "7") (name "GND2") (class "Default")
      (node (ref "5V_IN1") (pin "2") (pinfunction "S_2") (pintype "passive"))
      (node (ref "C10") (pin "2") (pinfunction "2_2") (pintype "passive"))
      (node (ref "C2") (pin "2") (pinfunction "2_2") (pintype "passive"))
      (node (ref "C3") (pin "2") (pinfunction "2_2") (pintype "passive"))
      (node (ref "C8") (pin "2") (pinfunction "2_2") (pintype "passive"))
      (node (ref "C9") (pin "2") (pinfunction "2_2") (pintype "passive"))
      (node (ref "IC3") (pin "2") (pinfunction "GND_2") (pintype "input"))
      (node (ref "IC3") (pin "4") (pinfunction "GND_4") (pintype "input"))
      (node (ref "U1") (pin "1") (pinfunction "GND_1") (pintype "passive"))
      (node (ref "US_1") (pin "1") (pinfunction "S_1") (pintype "passive"))
      (node (ref "US_1") (pin "6") (pinfunction "S_6") (pintype "passive"))
      (node (ref "US_2") (pin "1") (pinfunction "S_1") (pintype "passive"))
      (node (ref "US_2") (pin "6") (pinfunction "S_6") (pintype "passive"))
      (node (ref "US_3") (pin "1") (pinfunction "S_1") (pintype "passive"))
      (node (ref "US_3") (pin "6") (pinfunction "S_6") (pintype "passive"))
      (node (ref "US_4") (pin "1") (pinfunction "S_1") (pintype "passive"))
      (node (ref "US_4") (pin "6") (pinfunction "S_6") (pintype "passive"))
    )
    (net (code "8") (name "GND3") (class "Default")
      (node (ref "12V_IN") (pin "1") (pinfunction "1_1") (pintype "passive"))
      (node (ref "AX12-1") (pin "P$1") (pinfunction "1_P$1") (pintype "bidirectional"))
      (node (ref "AX12-2") (pin "P$1") (pinfunction "1_P$1") (pintype "bidirectional"))
      (node (ref "AX12-3") (pin "P$1") (pinfunction "1_P$1") (pintype "bidirectional"))
      (node (ref "AX12-4") (pin "P$1") (pinfunction "1_P$1") (pintype "bidirectional"))
      (node (ref "C5") (pin "2") (pinfunction "2_2") (pintype "passive"))
      (node (ref "C6") (pin "2") (pinfunction "2_2") (pintype "passive"))
      (node (ref "C7") (pin "2") (pinfunction "2_2") (pintype "passive"))
      (node (ref "IC1") (pin "3") (pinfunction "GND_3") (pintype "passive"))
      (node (ref "IC2") (pin "3") (pinfunction "GND_3") (pintype "passive"))
      (node (ref "SERVO1") (pin "1") (pinfunction "S_1") (pintype "passive"))
      (node (ref "SERVO2") (pin "1") (pinfunction "S_1") (pintype "passive"))
      (node (ref "SERVO3") (pin "1") (pinfunction "S_1") (pintype "passive"))
      (node (ref "SERVO4") (pin "1") (pinfunction "S_1") (pintype "passive"))
    )
    (net (code "9") (name "GND4") (class "Default")
      (node (ref "BAT_TEMP") (pin "1") (pinfunction "S_1") (pintype "passive"))
      (node (ref "C11") (pin "2") (pinfunction "2_2") (pintype "passive"))
      (node (ref "C13") (pin "1") (pinfunction "1_1") (pintype "passive"))
      (node (ref "C15") (pin "1") (pinfunction "1_1") (pintype "passive"))
      (node (ref "C16") (pin "1") (pinfunction "1_1") (pintype "passive"))
      (node (ref "C17") (pin "1") (pinfunction "1_1") (pintype "passive"))
      (node (ref "C19") (pin "1") (pinfunction "1_1") (pintype "passive"))
      (node (ref "C20") (pin "1") (pinfunction "1_1") (pintype "passive"))
      (node (ref "C23") (pin "1") (pinfunction "1_1") (pintype "passive"))
      (node (ref "C24") (pin "1") (pinfunction "1_1") (pintype "passive"))
      (node (ref "C25") (pin "1") (pinfunction "1_1") (pintype "passive"))
      (node (ref "C27") (pin "1") (pinfunction "1_1") (pintype "passive"))
      (node (ref "C28") (pin "1") (pinfunction "1_1") (pintype "passive"))
      (node (ref "CHARGER") (pin "17") (pinfunction "GND_17") (pintype "bidirectional"))
      (node (ref "CHARGER") (pin "THERMAL") (pinfunction "GND_THERMAL") (pintype "bidirectional"))
      (node (ref "DC_IN") (pin "1") (pinfunction "1_1") (pintype "passive"))
      (node (ref "DC_IN2") (pin "1") (pinfunction "1_1") (pintype "passive"))
      (node (ref "DC_IN2") (pin "2") (pinfunction "2_2") (pintype "passive"))
      (node (ref "OUT") (pin "1") (pinfunction "1_1") (pintype "passive"))
      (node (ref "Q7") (pin "2") (pinfunction "S_2") (pintype "passive"))
      (node (ref "R18") (pin "1") (pinfunction "1_1") (pintype "passive"))
      (node (ref "R19") (pin "1") (pinfunction "1_1") (pintype "passive"))
      (node (ref "R20") (pin "1") (pinfunction "1_1") (pintype "passive"))
      (node (ref "R22") (pin "2") (pinfunction "2_2") (pintype "passive"))
      (node (ref "R27") (pin "2") (pinfunction "2_2") (pintype "passive"))
      (node (ref "R44") (pin "2") (pinfunction "2_2") (pintype "passive"))
      (node (ref "R46") (pin "2") (pinfunction "2_2") (pintype "passive"))
    )
    (net (code "10") (name "GND5") (class "Default")
      (node (ref "BAT") (pin "1") (pinfunction "1_1") (pintype "passive"))
      (node (ref "C29") (pin "1") (pinfunction "1_1") (pintype "passive"))
      (node (ref "C30") (pin "1") (pinfunction "1_1") (pintype "passive"))
      (node (ref "C31") (pin "1") (pinfunction "1_1") (pintype "passive"))
      (node (ref "C32") (pin "1") (pinfunction "1_1") (pintype "passive"))
      (node (ref "C33") (pin "2") (pinfunction "2_2") (pintype "passive"))
      (node (ref "C34") (pin "2") (pinfunction "2_2") (pintype "passive"))
      (node (ref "C36") (pin "2") (pinfunction "2_2") (pintype "passive"))
      (node (ref "C39") (pin "1") (pinfunction "1_1") (pintype "passive"))
      (node (ref "C40") (pin "1") (pinfunction "1_1") (pintype "passive"))
      (node (ref "C50") (pin "2") (pinfunction "2_2") (pintype "passive"))
      (node (ref "C51") (pin "2") (pinfunction "2_2") (pintype "passive"))
      (node (ref "CCCAP") (pin "1") (pinfunction "1_1") (pintype "passive"))
      (node (ref "CDCAP") (pin "1") (pinfunction "1_1") (pintype "passive"))
      (node (ref "CVREG") (pin "1") (pinfunction "1_1") (pintype "passive"))
      (node (ref "GAUGE") (pin "14") (pinfunction "VSS_14") (pintype "bidirectional"))
      (node (ref "IC4") (pin "7") (pinfunction "GND_7") (pintype "power_in"))
      (node (ref "PGM_PWR") (pin "1") (pinfunction "S_1") (pintype "passive"))
      (node (ref "PROTECTION") (pin "11") (pinfunction "VSS2_11") (pintype "bidirectional"))
      (node (ref "PROTECTION") (pin "23") (pinfunction "GND_23") (pintype "bidirectional"))
      (node (ref "PROTECTION") (pin "24") (pinfunction "GND_24") (pintype "bidirectional"))
      (node (ref "PROTECTION") (pin "25") (pinfunction "GND_25") (pintype "bidirectional"))
      (node (ref "PROTECTION") (pin "29") (pinfunction "VSS1_29") (pintype "bidirectional"))
      (node (ref "Q8") (pin "2") (pinfunction "S_2") (pintype "passive"))
      (node (ref "R37") (pin "1") (pinfunction "1_1") (pintype "passive"))
      (node (ref "R51") (pin "2") (pinfunction "2_2") (pintype "passive"))
      (node (ref "RCPCKN") (pin "1") (pinfunction "1_1") (pintype "passive"))
      (node (ref "RLDRM_DET") (pin "2") (pinfunction "2_2") (pintype "passive"))
      (node (ref "U$2") (pin "2") (pinfunction "GND_2") (pintype "input"))
      (node (ref "U$2") (pin "4") (pinfunction "GND_4") (pintype "input"))
    )
    (net (code "11") (name "Net-(12V_INB-1)") (class "Default")
      (node (ref "12V_IN") (pin "2") (pinfunction "1_2") (pintype "passive"))
      (node (ref "AX12-1") (pin "P$2") (pinfunction "2_P$2") (pintype "bidirectional"))
      (node (ref "AX12-2") (pin "P$2") (pinfunction "2_P$2") (pintype "bidirectional"))
      (node (ref "AX12-3") (pin "P$2") (pinfunction "2_P$2") (pintype "bidirectional"))
      (node (ref "AX12-4") (pin "P$2") (pinfunction "2_P$2") (pintype "bidirectional"))
      (node (ref "C7") (pin "1") (pinfunction "1_1") (pintype "passive"))
      (node (ref "IC1") (pin "1") (pinfunction "VI_1") (pintype "input"))
      (node (ref "IC2") (pin "1") (pinfunction "VI_1") (pintype "input"))
    )
    (net (code "12") (name "Net-(AX12-1-3)") (class "Default")
      (node (ref "AX12-1") (pin "P$3") (pinfunction "3_P$3") (pintype "bidirectional"))
      (node (ref "AX12-2") (pin "P$3") (pinfunction "3_P$3") (pintype "bidirectional"))
      (node (ref "AX12-3") (pin "P$3") (pinfunction "3_P$3") (pintype "bidirectional"))
      (node (ref "AX12-4") (pin "P$3") (pinfunction "3_P$3") (pintype "bidirectional"))
      (node (ref "AX12-COMM") (pin "1") (pinfunction "S_1") (pintype "passive"))
      (node (ref "AX12-COMM") (pin "2") (pinfunction "S_2") (pintype "passive"))
    )
    (net (code "13") (name "Net-(BAT-CELLA-S)") (class "Default")
      (node (ref "BAT-CELL") (pin "1") (pinfunction "S_1") (pintype "passive"))
      (node (ref "RVC9") (pin "2") (pinfunction "2_2") (pintype "passive"))
    )
    (net (code "14") (name "Net-(BAT-CELLB-S)") (class "Default")
      (node (ref "BAT-CELL") (pin "2") (pinfunction "S_2") (pintype "passive"))
      (node (ref "RVC8") (pin "2") (pinfunction "2_2") (pintype "passive"))
    )
    (net (code "15") (name "Net-(BAT-CELLC-S)") (class "Default")
      (node (ref "BAT-CELL") (pin "3") (pinfunction "S_3") (pintype "passive"))
      (node (ref "RVC7") (pin "2") (pinfunction "2_2") (pintype "passive"))
    )
    (net (code "16") (name "Net-(BAT-CELLD-S)") (class "Default")
      (node (ref "BAT-CELL") (pin "4") (pinfunction "S_4") (pintype "passive"))
      (node (ref "RVC6") (pin "2") (pinfunction "2_2") (pintype "passive"))
    )
    (net (code "17") (name "Net-(BAT-CELLE-S)") (class "Default")
      (node (ref "BAT-CELL") (pin "5") (pinfunction "S_5") (pintype "passive"))
      (node (ref "RVC5") (pin "2") (pinfunction "2_2") (pintype "passive"))
    )
    (net (code "18") (name "Net-(BAT-CELLF-S)") (class "Default")
      (node (ref "BAT-CELL") (pin "6") (pinfunction "S_6") (pintype "passive"))
      (node (ref "RVC4") (pin "2") (pinfunction "2_2") (pintype "passive"))
    )
    (net (code "19") (name "Net-(BAT-CELLG-S)") (class "Default")
      (node (ref "BAT-CELL") (pin "7") (pinfunction "S_7") (pintype "passive"))
      (node (ref "RVC3") (pin "2") (pinfunction "2_2") (pintype "passive"))
    )
    (net (code "20") (name "Net-(BAT-CELLH-S)") (class "Default")
      (node (ref "BAT-CELL") (pin "8") (pinfunction "S_8") (pintype "passive"))
      (node (ref "RVC2") (pin "2") (pinfunction "2_2") (pintype "passive"))
    )
    (net (code "21") (name "Net-(BATB-1)") (class "Default")
      (node (ref "BAT") (pin "2") (pinfunction "1_2") (pintype "passive"))
      (node (ref "C18") (pin "1") (pinfunction "1_1") (pintype "passive"))
      (node (ref "C23") (pin "2") (pinfunction "2_2") (pintype "passive"))
      (node (ref "C24") (pin "2") (pinfunction "2_2") (pintype "passive"))
      (node (ref "C26") (pin "1") (pinfunction "1_1") (pintype "passive"))
      (node (ref "C50") (pin "1") (pinfunction "1_1") (pintype "passive"))
      (node (ref "CHARGER") (pin "13") (pinfunction "SRN_13") (pintype "bidirectional"))
      (node (ref "D2") (pin "A") (pinfunction "A_A") (pintype "passive"))
      (node (ref "Q5") (pin "3") (pinfunction "D_3") (pintype "passive"))
      (node (ref "R21") (pin "1") (pinfunction "1_1") (pintype "passive"))
      (node (ref "R25") (pin "1") (pinfunction "1_1") (pintype "passive"))
      (node (ref "R50") (pin "1") (pinfunction "1_1") (pintype "passive"))
      (node (ref "U$2") (pin "1") (pinfunction "IN_1") (pintype "input"))
    )
    (net (code "22") (name "Net-(BAT_TEMPB-S)") (class "Default")
      (node (ref "BAT_TEMP") (pin "2") (pinfunction "S_2") (pintype "passive"))
      (node (ref "R26") (pin "2") (pinfunction "2_2") (pintype "passive"))
      (node (ref "R27") (pin "1") (pinfunction "1_1") (pintype "passive"))
      (node (ref "R28") (pin "1") (pinfunction "1_1") (pintype "passive"))
    )
    (net (code "23") (name "Net-(C11-Pad1)") (class "Default")
      (node (ref "C11") (pin "1") (pinfunction "1_1") (pintype "passive"))
      (node (ref "R3") (pin "1") (pinfunction "1_1") (pintype "passive"))
      (node (ref "R52") (pin "1") (pinfunction "1_1") (pintype "passive"))
    )
    (net (code "24") (name "Net-(CHARGER-ACN)") (class "Default")
      (node (ref "C14") (pin "2") (pinfunction "2_2") (pintype "passive"))
      (node (ref "C19") (pin "2") (pinfunction "2_2") (pintype "passive"))
      (node (ref "C20") (pin "2") (pinfunction "2_2") (pintype "passive"))
      (node (ref "C21") (pin "1") (pinfunction "1_1") (pintype "passive"))
      (node (ref "CHARGER") (pin "1") (pinfunction "ACN_1") (pintype "bidirectional"))
      (node (ref "OUT") (pin "2") (pinfunction "1_2") (pintype "passive"))
      (node (ref "Q5") (pin "2") (pinfunction "S_2") (pintype "passive"))
      (node (ref "Q6") (pin "3") (pinfunction "D_3") (pintype "passive"))
      (node (ref "R23") (pin "1") (pinfunction "1_1") (pintype "passive"))
      (node (ref "R6") (pin "1") (pinfunction "1_1") (pintype "passive"))
    )
    (net (code "25") (name "Net-(CHARGER-ACP)") (class "Default")
      (node (ref "C14") (pin "1") (pinfunction "1_1") (pintype "passive"))
      (node (ref "C15") (pin "2") (pinfunction "2_2") (pintype "passive"))
      (node (ref "CHARGER") (pin "2") (pinfunction "ACP_2") (pintype "bidirectional"))
      (node (ref "Q4") (pin "3") (pinfunction "D_3") (pintype "passive"))
      (node (ref "R6") (pin "2") (pinfunction "2_2") (pintype "passive"))
    )
    (net (code "26") (name "Net-(CHARGER-ACSET)") (class "Default")
      (node (ref "CHARGER") (pin "16") (pinfunction "ACSET_16") (pintype "bidirectional"))
      (node (ref "R15") (pin "1") (pinfunction "1_1") (pintype "passive"))
      (node (ref "R18") (pin "2") (pinfunction "2_2") (pintype "passive"))
    )
    (net (code "27") (name "Net-(CHARGER-BTST)") (class "Default")
      (node (ref "C22") (pin "2") (pinfunction "2_2") (pintype "passive"))
      (node (ref "CHARGER") (pin "22") (pinfunction "BTST_22") (pintype "bidirectional"))
      (node (ref "D1") (pin "3") (pinfunction "C_3") (pintype "passive"))
    )
    (net (code "28") (name "Net-(CHARGER-CE)") (class "Default")
      (node (ref "C16") (pin "2") (pinfunction "2_2") (pintype "passive"))
      (node (ref "CHARGER") (pin "10") (pinfunction "VREF_10") (pintype "bidirectional"))
      (node (ref "CHARGER") (pin "4") (pinfunction "CE_4") (pintype "bidirectional"))
      (node (ref "R15") (pin "2") (pinfunction "2_2") (pintype "passive"))
      (node (ref "R16") (pin "2") (pinfunction "2_2") (pintype "passive"))
      (node (ref "R17") (pin "2") (pinfunction "2_2") (pintype "passive"))
      (node (ref "R26") (pin "1") (pinfunction "1_1") (pintype "passive"))
    )
    (net (code "29") (name "Net-(CHARGER-HIDRV)") (class "Default")
      (node (ref "CHARGER") (pin "21") (pinfunction "HIDRV_21") (pintype "bidirectional"))
      (node (ref "Q6") (pin "1") (pinfunction "G_1") (pintype "passive"))
    )
    (net (code "30") (name "Net-(CHARGER-ISET1)") (class "Default")
      (node (ref "CHARGER") (pin "11") (pinfunction "ISET1_11") (pintype "bidirectional"))
      (node (ref "R17") (pin "1") (pinfunction "1_1") (pintype "passive"))
      (node (ref "R20") (pin "2") (pinfunction "2_2") (pintype "passive"))
    )
    (net (code "31") (name "Net-(CHARGER-ISET2)") (class "Default")
      (node (ref "CHARGER") (pin "15") (pinfunction "ISET2_15") (pintype "bidirectional"))
      (node (ref "R16") (pin "1") (pinfunction "1_1") (pintype "passive"))
      (node (ref "R19") (pin "2") (pinfunction "2_2") (pintype "passive"))
    )
    (net (code "32") (name "Net-(CHARGER-LODRV)") (class "Default")
      (node (ref "CHARGER") (pin "19") (pinfunction "LODRV_19") (pintype "bidirectional"))
      (node (ref "Q7") (pin "1") (pinfunction "G_1") (pintype "passive"))
    )
    (net (code "33") (name "Net-(CHARGER-PH)") (class "Default")
      (node (ref "C22") (pin "1") (pinfunction "1_1") (pintype "passive"))
      (node (ref "CHARGER") (pin "20") (pinfunction "PH_20") (pintype "bidirectional"))
      (node (ref "L1") (pin "P$1") (pinfunction "P$1_P$1") (pintype "bidirectional"))
      (node (ref "Q6") (pin "2") (pinfunction "S_2") (pintype "passive"))
      (node (ref "Q7") (pin "3") (pinfunction "D_3") (pintype "passive"))
    )
    (net (code "34") (name "Net-(CHARGER-REGN)") (class "Default")
      (node (ref "C25") (pin "2") (pinfunction "2_2") (pintype "passive"))
      (node (ref "CHARGER") (pin "18") (pinfunction "REGN_18") (pintype "bidirectional"))
      (node (ref "D1") (pin "1") (pinfunction "A_1") (pintype "passive"))
    )
    (net (code "35") (name "Net-(CHARGER-SRP)") (class "Default")
      (node (ref "C26") (pin "2") (pinfunction "2_2") (pintype "passive"))
      (node (ref "C27") (pin "2") (pinfunction "2_2") (pintype "passive"))
      (node (ref "CHARGER") (pin "14") (pinfunction "SRP_14") (pintype "bidirectional"))
      (node (ref "L1") (pin "P$2") (pinfunction "P$2_P$2") (pintype "bidirectional"))
      (node (ref "R25") (pin "2") (pinfunction "2_2") (pintype "passive"))
    )
    (net (code "36") (name "Net-(CHARGER-STAT1)") (class "Default")
      (node (ref "CHARGER") (pin "5") (pinfunction "STAT1_5") (pintype "bidirectional"))
      (node (ref "LED1") (pin "C") (pinfunction "C_C") (pintype "passive"))
    )
    (net (code "37") (name "Net-(CHARGER-STAT2)") (class "Default")
      (node (ref "CHARGER") (pin "9") (pinfunction "STAT2_9") (pintype "bidirectional"))
      (node (ref "LED2") (pin "C") (pinfunction "C_C") (pintype "passive"))
    )
    (net (code "38") (name "Net-(CHARGER-TS)") (class "Default")
      (node (ref "C28") (pin "2") (pinfunction "2_2") (pintype "passive"))
      (node (ref "CHARGER") (pin "6") (pinfunction "TS_6") (pintype "bidirectional"))
      (node (ref "PROTECTION") (pin "13") (pinfunction "TS_13") (pintype "bidirectional"))
      (node (ref "PROTECTION") (pin "14") (pinfunction "CHGST_14") (pintype "bidirectional"))
      (node (ref "R28") (pin "2") (pinfunction "2_2") (pintype "passive"))
    )
    (net (code "39") (name "Net-(CHARGER-TTC)") (class "Default")
      (node (ref "C17") (pin "2") (pinfunction "2_2") (pintype "passive"))
      (node (ref "CHARGER") (pin "7") (pinfunction "TTC_7") (pintype "bidirectional"))
    )
    (net (code "40") (name "Net-(CHARGER-VCC)") (class "Default")
      (node (ref "C13") (pin "2") (pinfunction "2_2") (pintype "passive"))
      (node (ref "CHARGER") (pin "24") (pinfunction "VCC_24") (pintype "bidirectional"))
      (node (ref "R9") (pin "1") (pinfunction "1_1") (pintype "passive"))
    )
    (net (code "41") (name "Net-(CHARGER-VFB)") (class "Default")
      (node (ref "C18") (pin "2") (pinfunction "2_2") (pintype "passive"))
      (node (ref "CHARGER") (pin "12") (pinfunction "VFB_12") (pintype "bidirectional"))
      (node (ref "R21") (pin "2") (pinfunction "2_2") (pintype "passive"))
      (node (ref "R22") (pin "1") (pinfunction "1_1") (pintype "passive"))
    )
    (net (code "42") (name "Net-(CHARGER-~{ACDRV})") (class "Default")
      (node (ref "CHARGER") (pin "3") (pinfunction "~{ACDRV}_3") (pintype "bidirectional"))
      (node (ref "R5") (pin "1") (pinfunction "1_1") (pintype "passive"))
    )
    (net (code "43") (name "Net-(CHARGER-~{BATDRV})") (class "Default")
      (node (ref "CHARGER") (pin "23") (pinfunction "~{BATDRV}_23") (pintype "bidirectional"))
      (node (ref "R24") (pin "1") (pinfunction "1_1") (pintype "passive"))
    )
    (net (code "44") (name "Net-(CHARGER-~{PG})") (class "Default")
      (node (ref "CHARGER") (pin "8") (pinfunction "~{PG}_8") (pintype "bidirectional"))
      (node (ref "LED3") (pin "C") (pinfunction "C_C") (pintype "passive"))
    )
    (net (code "45") (name "Net-(ENCODER1C-S)") (class "Default")
      (node (ref "ENCODER1") (pin "3") (pinfunction "S_3") (pintype "passive"))
      (node (ref "U$1") (pin "P$8") (pinfunction "1A4_P$8") (pintype "bidirectional"))
    )
    (net (code "46") (name "Net-(ENCODER1D-S)") (class "Default")
      (node (ref "ENCODER1") (pin "4") (pinfunction "S_4") (pintype "passive"))
      (node (ref "U$1") (pin "P$6") (pinfunction "1A3_P$6") (pintype "bidirectional"))
    )
    (net (code "47") (name "Net-(ENCODER2C-S)") (class "Default")
      (node (ref "ENCODER2") (pin "3") (pinfunction "S_3") (pintype "passive"))
      (node (ref "U$1") (pin "P$4") (pinfunction "1A2_P$4") (pintype "bidirectional"))
    )
    (net (code "48") (name "Net-(ENCODER2D-S)") (class "Default")
      (node (ref "ENCODER2") (pin "4") (pinfunction "S_4") (pintype "passive"))
      (node (ref "U$1") (pin "P$2") (pinfunction "1A1_P$2") (pintype "bidirectional"))
    )
    (net (code "49") (name "Net-(ENCODER3C-S)") (class "Default")
      (node (ref "ENCODER3") (pin "3") (pinfunction "S_3") (pintype "passive"))
      (node (ref "R1") (pin "1") (pinfunction "1_1") (pintype "passive"))
      (node (ref "U$1") (pin "P$17") (pinfunction "2A4_P$17") (pintype "bidirectional"))
    )
    (net (code "50") (name "Net-(ENCODER3D-S)") (class "Default")
      (node (ref "ENCODER3") (pin "4") (pinfunction "S_4") (pintype "passive"))
      (node (ref "R2") (pin "1") (pinfunction "1_1") (pintype "passive"))
      (node (ref "U$1") (pin "P$15") (pinfunction "2A3_P$15") (pintype "bidirectional"))
    )
    (net (code "51") (name "Net-(ENCODER4C-S)") (class "Default")
      (node (ref "ENCODER4") (pin "3") (pinfunction "S_3") (pintype "passive"))
      (node (ref "R8") (pin "1") (pinfunction "1_1") (pintype "passive"))
      (node (ref "U$1") (pin "P$13") (pinfunction "2A2_P$13") (pintype "bidirectional"))
    )
    (net (code "52") (name "Net-(ENCODER4D-S)") (class "Default")
      (node (ref "ENCODER4") (pin "4") (pinfunction "S_4") (pintype "passive"))
      (node (ref "R7") (pin "1") (pinfunction "1_1") (pintype "passive"))
      (node (ref "U$1") (pin "P$11") (pinfunction "2A1_P$11") (pintype "bidirectional"))
    )
    (net (code "53") (name "Net-(GAUGE-BAT)") (class "Default")
      (node (ref "GAUGE") (pin "4") (pinfunction "BAT_4") (pintype "bidirectional"))
      (node (ref "R50") (pin "2") (pinfunction "2_2") (pintype "passive"))
      (node (ref "R51") (pin "1") (pinfunction "1_1") (pintype "passive"))
    )
    (net (code "54") (name "Net-(GAUGE-CE)") (class "Default")
      (node (ref "C29") (pin "2") (pinfunction "2_2") (pintype "passive"))
      (node (ref "C30") (pin "2") (pinfunction "2_2") (pintype "passive"))
      (node (ref "C51") (pin "1") (pinfunction "1_1") (pintype "passive"))
      (node (ref "GAUGE") (pin "5") (pinfunction "CE_5") (pintype "bidirectional"))
      (node (ref "GAUGE") (pin "6") (pinfunction "REGIN_6") (pintype "bidirectional"))
      (node (ref "IC4") (pin "14") (pinfunction "VCC_14") (pintype "power_in"))
      (node (ref "IC4") (pin "9") (pinfunction "CLR_9") (pintype "input"))
      (node (ref "R31") (pin "2") (pinfunction "2_2") (pintype "passive"))
      (node (ref "R32") (pin "2") (pinfunction "2_2") (pintype "passive"))
      (node (ref "R33") (pin "2") (pinfunction "2_2") (pintype "passive"))
      (node (ref "R34") (pin "2") (pinfunction "2_2") (pintype "passive"))
      (node (ref "R35") (pin "2") (pinfunction "2_2") (pintype "passive"))
      (node (ref "R40") (pin "2") (pinfunction "2_2") (pintype "passive"))
      (node (ref "R41") (pin "2") (pinfunction "2_2") (pintype "passive"))
      (node (ref "R42") (pin "2") (pinfunction "2_2") (pintype "passive"))
      (node (ref "U$2") (pin "3") (pinfunction "OUT_3") (pintype "passive"))
    )
    (net (code "55") (name "Net-(GAUGE-P1)") (class "Default")
      (node (ref "GAUGE") (pin "3") (pinfunction "P1_3") (pintype "bidirectional"))
      (node (ref "IC4") (pin "1") (pinfunction "A_1") (pintype "input"))
      (node (ref "IC4") (pin "2") (pinfunction "B_2") (pintype "input"))
    )
    (net (code "56") (name "Net-(GAUGE-P2)") (class "Default")
      (node (ref "GAUGE") (pin "1") (pinfunction "P2_1") (pintype "bidirectional"))
      (node (ref "IC4") (pin "8") (pinfunction "CLK_8") (pintype "input"))
    )
    (net (code "57") (name "Net-(GAUGE-P3{slash}SDA)") (class "Default")
      (node (ref "GAUGE") (pin "8") (pinfunction "P3/SDA_8") (pintype "bidirectional"))
      (node (ref "I2C_SELECT") (pin "2") (pinfunction "2_2") (pintype "passive"))
    )
    (net (code "58") (name "Net-(GAUGE-P4{slash}SCL)") (class "Default")
      (node (ref "GAUGE") (pin "9") (pinfunction "P4/SCL_9") (pintype "bidirectional"))
      (node (ref "I2C_PGM") (pin "1") (pinfunction "S_1") (pintype "passive"))
      (node (ref "PROTECTION") (pin "27") (pinfunction "SCLK_27") (pintype "bidirectional"))
      (node (ref "R30") (pin "2") (pinfunction "2_2") (pintype "passive"))
    )
    (net (code "59") (name "Net-(GAUGE-REG25)") (class "Default")
      (node (ref "C33") (pin "1") (pinfunction "1_1") (pintype "passive"))
      (node (ref "GAUGE") (pin "7") (pinfunction "REG25_7") (pintype "bidirectional"))
      (node (ref "R49") (pin "1") (pinfunction "1_1") (pintype "passive"))
    )
    (net (code "60") (name "Net-(GAUGE-SRN)") (class "Default")
      (node (ref "C31") (pin "2") (pinfunction "2_2") (pintype "passive"))
      (node (ref "GAUGE") (pin "12") (pinfunction "SRN_12") (pintype "bidirectional"))
      (node (ref "R48") (pin "1") (pinfunction "1_1") (pintype "passive"))
    )
    (net (code "61") (name "Net-(GAUGE-SRP)") (class "Default")
      (node (ref "C32") (pin "2") (pinfunction "2_2") (pintype "passive"))
      (node (ref "GAUGE") (pin "13") (pinfunction "SRP_13") (pintype "bidirectional"))
      (node (ref "R47") (pin "1") (pinfunction "1_1") (pintype "passive"))
    )
    (net (code "62") (name "Net-(GAUGE-VEN)") (class "Default")
      (node (ref "GAUGE") (pin "2") (pinfunction "VEN_2") (pintype "bidirectional"))
      (node (ref "VIEW_SOC") (pin "P$3") (pinfunction "P$2_P$3") (pintype "bidirectional"))
      (node (ref "VIEW_SOC") (pin "P$4") (pinfunction "P$2_P$4") (pintype "bidirectional"))
    )
    (net (code "63") (name "Net-(I2C_PGMB-S)") (class "Default")
      (node (ref "I2C_PGM") (pin "2") (pinfunction "S_2") (pintype "passive"))
      (node (ref "I2C_SELECT") (pin "1") (pinfunction "1_1") (pintype "passive"))
      (node (ref "R29") (pin "2") (pinfunction "2_2") (pintype "passive"))
    )
    (net (code "64") (name "Net-(IC1-VO)") (class "Default")
      (node (ref "C5") (pin "1") (pinfunction "1_1") (pintype "passive"))
      (node (ref "IC1") (pin "2") (pinfunction "VO_2") (pintype "passive"))
      (node (ref "SERVO1") (pin "2") (pinfunction "S_2") (pintype "passive"))
      (node (ref "SERVO2") (pin "2") (pinfunction "S_2") (pintype "passive"))
    )
    (net (code "65") (name "Net-(IC2-VO)") (class "Default")
      (node (ref "C6") (pin "1") (pinfunction "1_1") (pintype "passive"))
      (node (ref "IC2") (pin "2") (pinfunction "VO_2") (pintype "passive"))
      (node (ref "SERVO3") (pin "2") (pinfunction "S_2") (pintype "passive"))
      (node (ref "SERVO4") (pin "2") (pinfunction "S_2") (pintype "passive"))
    )
    (net (code "66") (name "Net-(IC4A-QA)") (class "Default")
      (node (ref "IC4") (pin "3") (pinfunction "QA_3") (pintype "output"))
      (node (ref "SOC_LED1") (pin "C") (pinfunction "C_C") (pintype "passive"))
    )
    (net (code "67") (name "Net-(IC4A-QB)") (class "Default")
      (node (ref "IC4") (pin "4") (pinfunction "QB_4") (pintype "output"))
      (node (ref "SOC_LED2") (pin "C") (pinfunction "C_C") (pintype "passive"))
    )
    (net (code "68") (name "Net-(IC4A-QC)") (class "Default")
      (node (ref "IC4") (pin "5") (pinfunction "QC_5") (pintype "output"))
      (node (ref "SOC_LED3") (pin "C") (pinfunction "C_C") (pintype "passive"))
    )
    (net (code "69") (name "Net-(IC4A-QD)") (class "Default")
      (node (ref "IC4") (pin "6") (pinfunction "QD_6") (pintype "output"))
      (node (ref "SOC_LED4") (pin "C") (pinfunction "C_C") (pintype "passive"))
    )
    (net (code "70") (name "Net-(IC4A-QE)") (class "Default")
      (node (ref "IC4") (pin "10") (pinfunction "QE_10") (pintype "output"))
      (node (ref "SOC_LED5") (pin "C") (pinfunction "C_C") (pintype "passive"))
    )
    (net (code "71") (name "Net-(IC4A-QF)") (class "Default")
      (node (ref "IC4") (pin "11") (pinfunction "QF_11") (pintype "output"))
      (node (ref "SOC_LED6") (pin "C") (pinfunction "C_C") (pintype "passive"))
    )
    (net (code "72") (name "Net-(IC4A-QG)") (class "Default")
      (node (ref "IC4") (pin "12") (pinfunction "QG_12") (pintype "output"))
      (node (ref "SOC_LED7") (pin "C") (pinfunction "C_C") (pintype "passive"))
    )
    (net (code "73") (name "Net-(IC4A-QH)") (class "Default")
      (node (ref "IC4") (pin "13") (pinfunction "QH_13") (pintype "output"))
      (node (ref "SOC_LED8") (pin "C") (pinfunction "C_C") (pintype "passive"))
    )
    (net (code "74") (name "Net-(LED1-PadA)") (class "Default")
      (node (ref "LED1") (pin "A") (pinfunction "A_A") (pintype "passive"))
      (node (ref "R10") (pin "1") (pinfunction "1_1") (pintype "passive"))
    )
    (net (code "75") (name "Net-(LED2-PadA)") (class "Default")
      (node (ref "LED2") (pin "A") (pinfunction "A_A") (pintype "passive"))
      (node (ref "R13") (pin "1") (pinfunction "1_1") (pintype "passive"))
    )
    (net (code "76") (name "Net-(LED3-PadA)") (class "Default")
      (node (ref "LED3") (pin "A") (pinfunction "A_A") (pintype "passive"))
      (node (ref "R14") (pin "1") (pinfunction "1_1") (pintype "passive"))
    )
    (net (code "77") (name "Net-(PGM_PWRB-S)") (class "Default")
      (node (ref "PGM_PWR") (pin "2") (pinfunction "S_2") (pintype "passive"))
      (node (ref "PROTECTION") (pin "28") (pinfunction "EEPROM_28") (pintype "bidirectional"))
    )
    (net (code "78") (name "Net-(PROTECTION-BAT)") (class "Default")
      (node (ref "C34") (pin "1") (pinfunction "1_1") (pintype "passive"))
      (node (ref "C36") (pin "1") (pinfunction "1_1") (pintype "passive"))
      (node (ref "D2") (pin "C") (pinfunction "C_C") (pintype "passive"))
      (node (ref "PROTECTION") (pin "31") (pinfunction "BAT_31") (pintype "bidirectional"))
    )
    (net (code "79") (name "Net-(PROTECTION-CCAP)") (class "Default")
      (node (ref "CCCAP") (pin "2") (pinfunction "2_2") (pintype "passive"))
      (node (ref "PROTECTION") (pin "20") (pinfunction "CCAP_20") (pintype "bidirectional"))
    )
    (net (code "80") (name "Net-(PROTECTION-CHG)") (class "Default")
      (node (ref "PROTECTION") (pin "21") (pinfunction "CHG_21") (pintype "bidirectional"))
      (node (ref "Q8") (pin "1") (pinfunction "G_1") (pintype "passive"))
      (node (ref "R37") (pin "2") (pinfunction "2_2") (pintype "passive"))
    )
    (net (code "81") (name "Net-(PROTECTION-CPCKN)") (class "Default")
      (node (ref "PROTECTION") (pin "19") (pinfunction "CPCKN_19") (pintype "bidirectional"))
      (node (ref "RCPCKN") (pin "2") (pinfunction "2_2") (pintype "passive"))
    )
    (net (code "82") (name "Net-(PROTECTION-DCAP)") (class "Default")
      (node (ref "CDCAP") (pin "2") (pinfunction "2_2") (pintype "passive"))
      (node (ref "PROTECTION") (pin "16") (pinfunction "DCAP_16") (pintype "bidirectional"))
    )
    (net (code "83") (name "Net-(PROTECTION-DPCKN)") (class "Default")
      (node (ref "PROTECTION") (pin "18") (pinfunction "DPCKN_18") (pintype "bidirectional"))
      (node (ref "RDPCKN") (pin "2") (pinfunction "2_2") (pintype "passive"))
      (node (ref "RLDRM_DET") (pin "1") (pinfunction "1_1") (pintype "passive"))
    )
    (net (code "84") (name "Net-(PROTECTION-DSG)") (class "Default")
      (node (ref "PROTECTION") (pin "17") (pinfunction "DSG_17") (pintype "bidirectional"))
      (node (ref "R39") (pin "2") (pinfunction "2_2") (pintype "passive"))
    )
    (net (code "85") (name "Net-(PROTECTION-SDATA)") (class "Default")
      (node (ref "I2C_SELECT") (pin "3") (pinfunction "3_3") (pintype "passive"))
      (node (ref "PROTECTION") (pin "26") (pinfunction "SDATA_26") (pintype "bidirectional"))
    )
    (net (code "86") (name "Net-(PROTECTION-SENSE+)") (class "Default")
      (node (ref "C39") (pin "2") (pinfunction "2_2") (pintype "passive"))
      (node (ref "PROTECTION") (pin "10") (pinfunction "SENSE+_10") (pintype "bidirectional"))
      (node (ref "R45") (pin "1") (pinfunction "1_1") (pintype "passive"))
    )
    (net (code "87") (name "Net-(PROTECTION-SENSE-)") (class "Default")
      (node (ref "C40") (pin "2") (pinfunction "2_2") (pintype "passive"))
      (node (ref "PROTECTION") (pin "9") (pinfunction "SENSE-_9") (pintype "bidirectional"))
      (node (ref "R44") (pin "1") (pinfunction "1_1") (pintype "passive"))
    )
    (net (code "88") (name "Net-(PROTECTION-VC1)") (class "Default")
      (node (ref "PROTECTION") (pin "34") (pinfunction "VC1_34") (pintype "bidirectional"))
      (node (ref "R36") (pin "1") (pinfunction "1_1") (pintype "passive"))
    )
    (net (code "89") (name "Net-(PROTECTION-VC2)") (class "Default")
      (node (ref "CVC2") (pin "1") (pinfunction "1_1") (pintype "passive"))
      (node (ref "PROTECTION") (pin "36") (pinfunction "VC2_36") (pintype "bidirectional"))
      (node (ref "R36") (pin "2") (pinfunction "2_2") (pintype "passive"))
      (node (ref "RVC2") (pin "1") (pinfunction "1_1") (pintype "passive"))
    )
    (net (code "90") (name "Net-(PROTECTION-VC3)") (class "Default")
      (node (ref "CVC2") (pin "2") (pinfunction "2_2") (pintype "passive"))
      (node (ref "CVC3") (pin "1") (pinfunction "1_1") (pintype "passive"))
      (node (ref "PROTECTION") (pin "38") (pinfunction "VC3_38") (pintype "bidirectional"))
      (node (ref "RVC3") (pin "1") (pinfunction "1_1") (pintype "passive"))
    )
    (net (code "91") (name "Net-(PROTECTION-VC4)") (class "Default")
      (node (ref "CVC3") (pin "2") (pinfunction "2_2") (pintype "passive"))
      (node (ref "CVC4") (pin "1") (pinfunction "1_1") (pintype "passive"))
      (node (ref "PROTECTION") (pin "1") (pinfunction "VC4_1") (pintype "bidirectional"))
      (node (ref "RVC4") (pin "1") (pinfunction "1_1") (pintype "passive"))
    )
    (net (code "92") (name "Net-(PROTECTION-VC5)") (class "Default")
      (node (ref "CVC4") (pin "2") (pinfunction "2_2") (pintype "passive"))
      (node (ref "CVC5") (pin "1") (pinfunction "1_1") (pintype "passive"))
      (node (ref "PROTECTION") (pin "3") (pinfunction "VC5_3") (pintype "bidirectional"))
      (node (ref "RVC5") (pin "1") (pinfunction "1_1") (pintype "passive"))
    )
    (net (code "93") (name "Net-(PROTECTION-VC6)") (class "Default")
      (node (ref "CVC5") (pin "2") (pinfunction "2_2") (pintype "passive"))
      (node (ref "CVC6") (pin "1") (pinfunction "1_1") (pintype "passive"))
      (node (ref "PROTECTION") (pin "5") (pinfunction "VC6_5") (pintype "bidirectional"))
      (node (ref "RVC6") (pin "1") (pinfunction "1_1") (pintype "passive"))
    )
    (net (code "94") (name "Net-(PROTECTION-VC7)") (class "Default")
      (node (ref "CVC6") (pin "2") (pinfunction "2_2") (pintype "passive"))
      (node (ref "CVC7") (pin "1") (pinfunction "1_1") (pintype "passive"))
      (node (ref "PROTECTION") (pin "6") (pinfunction "VC7_6") (pintype "bidirectional"))
      (node (ref "RVC7") (pin "1") (pinfunction "1_1") (pintype "passive"))
    )
    (net (code "95") (name "Net-(PROTECTION-VC8)") (class "Default")
      (node (ref "CVC7") (pin "2") (pinfunction "2_2") (pintype "passive"))
      (node (ref "CVC8") (pin "1") (pinfunction "1_1") (pintype "passive"))
      (node (ref "PROTECTION") (pin "7") (pinfunction "VC8_7") (pintype "bidirectional"))
      (node (ref "RVC8") (pin "1") (pinfunction "1_1") (pintype "passive"))
    )
    (net (code "96") (name "Net-(PROTECTION-VC9)") (class "Default")
      (node (ref "CVC8") (pin "2") (pinfunction "2_2") (pintype "passive"))
      (node (ref "PROTECTION") (pin "8") (pinfunction "VC9_8") (pintype "bidirectional"))
      (node (ref "RVC9") (pin "1") (pinfunction "1_1") (pintype "passive"))
    )
    (net (code "97") (name "Net-(PROTECTION-VREG)") (class "Default")
      (node (ref "CVREG") (pin "2") (pinfunction "2_2") (pintype "passive"))
      (node (ref "PGM_ENABLE") (pin "1") (pinfunction "1_1") (pintype "passive"))
      (node (ref "PROTECTION") (pin "12") (pinfunction "VREG_12") (pintype "bidirectional"))
      (node (ref "R29") (pin "1") (pinfunction "1_1") (pintype "passive"))
      (node (ref "R30") (pin "1") (pinfunction "1_1") (pintype "passive"))
    )
    (net (code "98") (name "Net-(PROTECTION-ZEDE)") (class "Default")
      (node (ref "PGM_ENABLE") (pin "2") (pinfunction "2_2") (pintype "passive"))
      (node (ref "PROTECTION") (pin "22") (pinfunction "ZEDE_22") (pintype "bidirectional"))
    )
    (net (code "99") (name "Net-(Q1-B)") (class "Default")
      (node (ref "Q1") (pin "1") (pinfunction "B_1") (pintype "passive"))
      (node (ref "R11") (pin "1") (pinfunction "1_1") (pintype "passive"))
    )
    (net (code "100") (name "Net-(Q1-C)") (class "Default")
      (node (ref "Q1") (pin "3") (pinfunction "C_3") (pintype "passive"))
      (node (ref "US_1") (pin "3") (pinfunction "S_3") (pintype "passive"))
    )
    (net (code "101") (name "Net-(Q2-B)") (class "Default")
      (node (ref "Q2") (pin "1") (pinfunction "B_1") (pintype "passive"))
      (node (ref "R12") (pin "1") (pinfunction "1_1") (pintype "passive"))
    )
    (net (code "102") (name "Net-(Q2-C)") (class "Default")
      (node (ref "Q2") (pin "3") (pinfunction "C_3") (pintype "passive"))
      (node (ref "US_3") (pin "3") (pinfunction "S_3") (pintype "passive"))
    )
    (net (code "103") (name "Net-(Q3-G)") (class "Default")
      (node (ref "C12") (pin "2") (pinfunction "2_2") (pintype "passive"))
      (node (ref "Q3") (pin "1") (pinfunction "G_1") (pintype "passive"))
      (node (ref "Q4") (pin "1") (pinfunction "G_1") (pintype "passive"))
      (node (ref "R4") (pin "1") (pinfunction "1_1") (pintype "passive"))
      (node (ref "R5") (pin "2") (pinfunction "2_2") (pintype "passive"))
    )
    (net (code "104") (name "Net-(Q3-S)") (class "Default")
      (node (ref "C12") (pin "1") (pinfunction "1_1") (pintype "passive"))
      (node (ref "Q3") (pin "2") (pinfunction "S_2") (pintype "passive"))
      (node (ref "Q4") (pin "2") (pinfunction "S_2") (pintype "passive"))
      (node (ref "R4") (pin "2") (pinfunction "2_2") (pintype "passive"))
      (node (ref "R9") (pin "2") (pinfunction "2_2") (pintype "passive"))
    )
    (net (code "105") (name "Net-(Q5-G)") (class "Default")
      (node (ref "C21") (pin "2") (pinfunction "2_2") (pintype "passive"))
      (node (ref "Q5") (pin "1") (pinfunction "G_1") (pintype "passive"))
      (node (ref "R23") (pin "2") (pinfunction "2_2") (pintype "passive"))
      (node (ref "R24") (pin "2") (pinfunction "2_2") (pintype "passive"))
    )
    (net (code "106") (name "Net-(Q8-D)") (class "Default")
      (node (ref "Q8") (pin "3") (pinfunction "D_3") (pintype "passive"))
      (node (ref "Q9") (pin "3") (pinfunction "D_3") (pintype "passive"))
      (node (ref "RDPCKN") (pin "1") (pinfunction "1_1") (pintype "passive"))
    )
    (net (code "107") (name "Net-(Q9-G)") (class "Default")
      (node (ref "Q9") (pin "1") (pinfunction "G_1") (pintype "passive"))
      (node (ref "R38") (pin "2") (pinfunction "2_2") (pintype "passive"))
      (node (ref "R39") (pin "1") (pinfunction "1_1") (pintype "passive"))
    )
    (net (code "108") (name "Net-(Q9-S)") (class "Default")
      (node (ref "Q9") (pin "2") (pinfunction "S_2") (pintype "passive"))
      (node (ref "R38") (pin "1") (pinfunction "1_1") (pintype "passive"))
      (node (ref "R43") (pin "1") (pinfunction "1_1") (pintype "passive"))
      (node (ref "R47") (pin "2") (pinfunction "2_2") (pintype "passive"))
    )
    (net (code "109") (name "Net-(QG1-OUT)") (class "Default")
      (node (ref "P4") (pin "14") (pinfunction "14_14") (pintype "passive"))
      (node (ref "QG1") (pin "3") (pinfunction "OUT_3") (pintype "output"))
    )
    (net (code "110") (name "Net-(R31-Pad1)") (class "Default")
      (node (ref "R31") (pin "1") (pinfunction "1_1") (pintype "passive"))
      (node (ref "SOC_LED1") (pin "A") (pinfunction "A_A") (pintype "passive"))
    )
    (net (code "111") (name "Net-(R32-Pad1)") (class "Default")
      (node (ref "R32") (pin "1") (pinfunction "1_1") (pintype "passive"))
      (node (ref "SOC_LED2") (pin "A") (pinfunction "A_A") (pintype "passive"))
    )
    (net (code "112") (name "Net-(R33-Pad1)") (class "Default")
      (node (ref "R33") (pin "1") (pinfunction "1_1") (pintype "passive"))
      (node (ref "SOC_LED3") (pin "A") (pinfunction "A_A") (pintype "passive"))
    )
    (net (code "113") (name "Net-(R34-Pad1)") (class "Default")
      (node (ref "R34") (pin "1") (pinfunction "1_1") (pintype "passive"))
      (node (ref "SOC_LED4") (pin "A") (pinfunction "A_A") (pintype "passive"))
    )
    (net (code "114") (name "Net-(R35-Pad1)") (class "Default")
      (node (ref "R35") (pin "1") (pinfunction "1_1") (pintype "passive"))
      (node (ref "SOC_LED5") (pin "A") (pinfunction "A_A") (pintype "passive"))
    )
    (net (code "115") (name "Net-(R40-Pad1)") (class "Default")
      (node (ref "R40") (pin "1") (pinfunction "1_1") (pintype "passive"))
      (node (ref "SOC_LED6") (pin "A") (pinfunction "A_A") (pintype "passive"))
    )
    (net (code "116") (name "Net-(R41-Pad1)") (class "Default")
      (node (ref "R41") (pin "1") (pinfunction "1_1") (pintype "passive"))
      (node (ref "SOC_LED7") (pin "A") (pinfunction "A_A") (pintype "passive"))
    )
    (net (code "117") (name "Net-(R42-Pad1)") (class "Default")
      (node (ref "R42") (pin "1") (pinfunction "1_1") (pintype "passive"))
      (node (ref "SOC_LED8") (pin "A") (pinfunction "A_A") (pintype "passive"))
    )
    (net (code "118") (name "Net-(R43-Pad2)") (class "Default")
      (node (ref "R43") (pin "2") (pinfunction "2_2") (pintype "passive"))
      (node (ref "R45") (pin "2") (pinfunction "2_2") (pintype "passive"))
      (node (ref "R46") (pin "1") (pinfunction "1_1") (pintype "passive"))
      (node (ref "R48") (pin "2") (pinfunction "2_2") (pintype "passive"))
    )
    (net (code "119") (name "Net-(R49-Pad2)") (class "Default")
      (node (ref "R49") (pin "2") (pinfunction "2_2") (pintype "passive"))
      (node (ref "VIEW_SOC") (pin "P$1") (pinfunction "P$1_P$1") (pintype "bidirectional"))
      (node (ref "VIEW_SOC") (pin "P$2") (pinfunction "P$1_P$2") (pintype "bidirectional"))
    )
    (net (code "120") (name "Net-(SERVO1C-S)") (class "Default")
      (node (ref "SERVO1") (pin "3") (pinfunction "S_3") (pintype "passive"))
      (node (ref "SERVO_PWM") (pin "1") (pinfunction "S_1") (pintype "passive"))
    )
    (net (code "121") (name "Net-(SERVO2C-S)") (class "Default")
      (node (ref "SERVO2") (pin "3") (pinfunction "S_3") (pintype "passive"))
      (node (ref "SERVO_PWM") (pin "2") (pinfunction "S_2") (pintype "passive"))
    )
    (net (code "122") (name "Net-(SERVO3C-S)") (class "Default")
      (node (ref "SERVO3") (pin "3") (pinfunction "S_3") (pintype "passive"))
      (node (ref "SERVO_PWM") (pin "3") (pinfunction "S_3") (pintype "passive"))
    )
    (net (code "123") (name "Net-(SERVO4C-S)") (class "Default")
      (node (ref "SERVO4") (pin "3") (pinfunction "S_3") (pintype "passive"))
      (node (ref "SERVO_PWM") (pin "4") (pinfunction "S_4") (pintype "passive"))
    )
    (net (code "124") (name "Net-(U$1-1Y1)") (class "Default")
      (node (ref "P4") (pin "15") (pinfunction "15_15") (pintype "passive"))
      (node (ref "U$1") (pin "P$18") (pinfunction "1Y1_P$18") (pintype "bidirectional"))
    )
    (net (code "125") (name "Net-(U$1-1Y2)") (class "Default")
      (node (ref "P4") (pin "21") (pinfunction "21_21") (pintype "passive"))
      (node (ref "U$1") (pin "P$16") (pinfunction "1Y2_P$16") (pintype "bidirectional"))
    )
    (net (code "126") (name "Net-(U$1-1Y3)") (class "Default")
      (node (ref "P4") (pin "22") (pinfunction "22_22") (pintype "passive"))
      (node (ref "U$1") (pin "P$14") (pinfunction "1Y3_P$14") (pintype "bidirectional"))
    )
    (net (code "127") (name "Net-(U$1-1Y4)") (class "Default")
      (node (ref "P4") (pin "23") (pinfunction "23_23") (pintype "passive"))
      (node (ref "U$1") (pin "P$12") (pinfunction "1Y4_P$12") (pintype "bidirectional"))
    )
    (net (code "128") (name "Net-(U$1-2Y1)") (class "Default")
      (node (ref "P1") (pin "1") (pinfunction "1_1") (pintype "passive"))
      (node (ref "U$1") (pin "P$9") (pinfunction "2Y1_P$9") (pintype "bidirectional"))
    )
    (net (code "129") (name "Net-(U$1-2Y2)") (class "Default")
      (node (ref "P1") (pin "2") (pinfunction "2_2") (pintype "passive"))
      (node (ref "U$1") (pin "P$7") (pinfunction "2Y2_P$7") (pintype "bidirectional"))
    )
    (net (code "130") (name "Net-(U$1-2Y3)") (class "Default")
      (node (ref "P1") (pin "3") (pinfunction "3_3") (pintype "passive"))
      (node (ref "U$1") (pin "P$5") (pinfunction "2Y3_P$5") (pintype "bidirectional"))
    )
    (net (code "131") (name "Net-(U$1-2Y4)") (class "Default")
      (node (ref "P1") (pin "4") (pinfunction "4_4") (pintype "passive"))
      (node (ref "U$1") (pin "P$3") (pinfunction "2Y4_P$3") (pintype "bidirectional"))
    )
    (net (code "132") (name "Net-(U1-CONTROL_VTG)") (class "Default")
      (node (ref "C2") (pin "1") (pinfunction "1_1") (pintype "passive"))
      (node (ref "U1") (pin "5") (pinfunction "CONTROL_VTG_5") (pintype "input"))
    )
    (net (code "133") (name "Net-(U1-DISCHARGE)") (class "Default")
      (node (ref "RA") (pin "1") (pinfunction "1_1") (pintype "passive"))
      (node (ref "RB") (pin "2") (pinfunction "2_2") (pintype "passive"))
      (node (ref "U1") (pin "7") (pinfunction "DISCHARGE_7") (pintype "input"))
    )
    (net (code "134") (name "Net-(U1-OUT)") (class "Default")
      (node (ref "R11") (pin "2") (pinfunction "2_2") (pintype "passive"))
      (node (ref "R12") (pin "2") (pinfunction "2_2") (pintype "passive"))
      (node (ref "U1") (pin "3") (pinfunction "OUT_3") (pintype "output"))
    )
    (net (code "135") (name "Net-(U1-TRESHOLD)") (class "Default")
      (node (ref "C3") (pin "1") (pinfunction "1_1") (pintype "passive"))
      (node (ref "RB") (pin "1") (pinfunction "1_1") (pintype "passive"))
      (node (ref "U1") (pin "2") (pinfunction "TRIGGER_2") (pintype "input"))
      (node (ref "U1") (pin "6") (pinfunction "TRESHOLD_6") (pintype "input"))
    )
    (net (code "136") (name "Net-(US_1B-S)") (class "Default")
      (node (ref "US_1") (pin "2") (pinfunction "S_2") (pintype "passive"))
      (node (ref "US_OUTPUT") (pin "1") (pinfunction "S_1") (pintype "passive"))
    )
    (net (code "137") (name "Net-(US_1D-S)") (class "Default")
      (node (ref "US_1") (pin "4") (pinfunction "S_4") (pintype "passive"))
      (node (ref "US_2") (pin "3") (pinfunction "S_3") (pintype "passive"))
    )
    (net (code "138") (name "Net-(US_2B-S)") (class "Default")
      (node (ref "US_2") (pin "2") (pinfunction "S_2") (pintype "passive"))
      (node (ref "US_OUTPUT") (pin "2") (pinfunction "S_2") (pintype "passive"))
    )
    (net (code "139") (name "Net-(US_3B-S)") (class "Default")
      (node (ref "US_3") (pin "2") (pinfunction "S_2") (pintype "passive"))
      (node (ref "US_OUTPUT") (pin "3") (pinfunction "S_3") (pintype "passive"))
    )
    (net (code "140") (name "Net-(US_3D-S)") (class "Default")
      (node (ref "US_3") (pin "4") (pinfunction "S_4") (pintype "passive"))
      (node (ref "US_4") (pin "3") (pinfunction "S_3") (pintype "passive"))
    )
    (net (code "141") (name "Net-(US_4B-S)") (class "Default")
      (node (ref "US_4") (pin "2") (pinfunction "S_2") (pintype "passive"))
      (node (ref "US_OUTPUT") (pin "4") (pinfunction "S_4") (pintype "passive"))
    )
    (net (code "142") (name "unconnected-(GAUGE-P5{slash}HDQ-Pad10)") (class "Default")
      (node (ref "GAUGE") (pin "10") (pinfunction "P5/HDQ_10") (pintype "bidirectional"))
    )
    (net (code "143") (name "unconnected-(GAUGE-P6{slash}TS-Pad11)") (class "Default")
      (node (ref "GAUGE") (pin "11") (pinfunction "P6/TS_11") (pintype "bidirectional"))
    )
    (net (code "144") (name "unconnected-(P1-Pad5)") (class "Default")
      (node (ref "P1") (pin "5") (pinfunction "5_5") (pintype "passive"))
    )
    (net (code "145") (name "unconnected-(P1-Pad6)") (class "Default")
      (node (ref "P1") (pin "6") (pinfunction "6_6") (pintype "passive"))
    )
    (net (code "146") (name "unconnected-(P1-Pad7)") (class "Default")
      (node (ref "P1") (pin "7") (pinfunction "7_7") (pintype "passive"))
    )
    (net (code "147") (name "unconnected-(P1-Pad8)") (class "Default")
      (node (ref "P1") (pin "8") (pinfunction "8_8") (pintype "passive"))
    )
    (net (code "148") (name "unconnected-(P1-Pad9)") (class "Default")
      (node (ref "P1") (pin "9") (pinfunction "9_9") (pintype "passive"))
    )
    (net (code "149") (name "unconnected-(P1-Pad10)") (class "Default")
      (node (ref "P1") (pin "10") (pinfunction "10_10") (pintype "passive"))
    )
    (net (code "150") (name "unconnected-(P1-Pad11)") (class "Default")
      (node (ref "P1") (pin "11") (pinfunction "11_11") (pintype "passive"))
    )
    (net (code "151") (name "unconnected-(P1-Pad12)") (class "Default")
      (node (ref "P1") (pin "12") (pinfunction "12_12") (pintype "passive"))
    )
    (net (code "152") (name "unconnected-(P1-Pad13)") (class "Default")
      (node (ref "P1") (pin "13") (pinfunction "13_13") (pintype "passive"))
    )
    (net (code "153") (name "unconnected-(P1-Pad14)") (class "Default")
      (node (ref "P1") (pin "14") (pinfunction "14_14") (pintype "passive"))
    )
    (net (code "154") (name "unconnected-(P1-Pad15)") (class "Default")
      (node (ref "P1") (pin "15") (pinfunction "15_15") (pintype "passive"))
    )
    (net (code "155") (name "unconnected-(P1-Pad16)") (class "Default")
      (node (ref "P1") (pin "16") (pinfunction "16_16") (pintype "passive"))
    )
    (net (code "156") (name "unconnected-(P3-Pad1)") (class "Default")
      (node (ref "P3") (pin "1") (pinfunction "1_1") (pintype "passive"))
    )
    (net (code "157") (name "unconnected-(P3-Pad2)") (class "Default")
      (node (ref "P3") (pin "2") (pinfunction "2_2") (pintype "passive"))
    )
    (net (code "158") (name "unconnected-(P3-Pad3)") (class "Default")
      (node (ref "P3") (pin "3") (pinfunction "3_3") (pintype "passive"))
    )
    (net (code "159") (name "unconnected-(P3-Pad4)") (class "Default")
      (node (ref "P3") (pin "4") (pinfunction "4_4") (pintype "passive"))
    )
    (net (code "160") (name "unconnected-(P3-Pad5)") (class "Default")
      (node (ref "P3") (pin "5") (pinfunction "5_5") (pintype "passive"))
    )
    (net (code "161") (name "unconnected-(P3-Pad6)") (class "Default")
      (node (ref "P3") (pin "6") (pinfunction "6_6") (pintype "passive"))
    )
    (net (code "162") (name "unconnected-(P3-Pad7)") (class "Default")
      (node (ref "P3") (pin "7") (pinfunction "7_7") (pintype "passive"))
    )
    (net (code "163") (name "unconnected-(P3-Pad8)") (class "Default")
      (node (ref "P3") (pin "8") (pinfunction "8_8") (pintype "passive"))
    )
    (net (code "164") (name "unconnected-(P3-Pad9)") (class "Default")
      (node (ref "P3") (pin "9") (pinfunction "9_9") (pintype "passive"))
    )
    (net (code "165") (name "unconnected-(P3-Pad10)") (class "Default")
      (node (ref "P3") (pin "10") (pinfunction "10_10") (pintype "passive"))
    )
    (net (code "166") (name "unconnected-(P3-Pad11)") (class "Default")
      (node (ref "P3") (pin "11") (pinfunction "11_11") (pintype "passive"))
    )
    (net (code "167") (name "unconnected-(P3-Pad12)") (class "Default")
      (node (ref "P3") (pin "12") (pinfunction "12_12") (pintype "passive"))
    )
    (net (code "168") (name "unconnected-(P3-Pad13)") (class "Default")
      (node (ref "P3") (pin "13") (pinfunction "13_13") (pintype "passive"))
    )
    (net (code "169") (name "unconnected-(P3-Pad14)") (class "Default")
      (node (ref "P3") (pin "14") (pinfunction "14_14") (pintype "passive"))
    )
    (net (code "170") (name "unconnected-(P3-Pad15)") (class "Default")
      (node (ref "P3") (pin "15") (pinfunction "15_15") (pintype "passive"))
    )
    (net (code "171") (name "unconnected-(P3-Pad16)") (class "Default")
      (node (ref "P3") (pin "16") (pinfunction "16_16") (pintype "passive"))
    )
    (net (code "172") (name "unconnected-(P4-Pad1)") (class "Default")
      (node (ref "P4") (pin "1") (pinfunction "1_1") (pintype "passive"))
    )
    (net (code "173") (name "unconnected-(P4-Pad2)") (class "Default")
      (node (ref "P4") (pin "2") (pinfunction "2_2") (pintype "passive"))
    )
    (net (code "174") (name "unconnected-(P4-Pad3)") (class "Default")
      (node (ref "P4") (pin "3") (pinfunction "3_3") (pintype "passive"))
    )
    (net (code "175") (name "unconnected-(P4-Pad4)") (class "Default")
      (node (ref "P4") (pin "4") (pinfunction "4_4") (pintype "passive"))
    )
    (net (code "176") (name "unconnected-(P4-Pad5)") (class "Default")
      (node (ref "P4") (pin "5") (pinfunction "5_5") (pintype "passive"))
    )
    (net (code "177") (name "unconnected-(P4-Pad6)") (class "Default")
      (node (ref "P4") (pin "6") (pinfunction "6_6") (pintype "passive"))
    )
    (net (code "178") (name "unconnected-(P4-Pad7)") (class "Default")
      (node (ref "P4") (pin "7") (pinfunction "7_7") (pintype "passive"))
    )
    (net (code "179") (name "unconnected-(P4-Pad8)") (class "Default")
      (node (ref "P4") (pin "8") (pinfunction "8_8") (pintype "passive"))
    )
    (net (code "180") (name "unconnected-(P4-Pad9)") (class "Default")
      (node (ref "P4") (pin "9") (pinfunction "9_9") (pintype "passive"))
    )
    (net (code "181") (name "unconnected-(P4-Pad10)") (class "Default")
      (node (ref "P4") (pin "10") (pinfunction "10_10") (pintype "passive"))
    )
    (net (code "182") (name "unconnected-(P4-Pad11)") (class "Default")
      (node (ref "P4") (pin "11") (pinfunction "11_11") (pintype "passive"))
    )
    (net (code "183") (name "unconnected-(P4-Pad12)") (class "Default")
      (node (ref "P4") (pin "12") (pinfunction "12_12") (pintype "passive"))
    )
    (net (code "184") (name "unconnected-(P4-Pad13)") (class "Default")
      (node (ref "P4") (pin "13") (pinfunction "13_13") (pintype "passive"))
    )
    (net (code "185") (name "unconnected-(P4-Pad16)") (class "Default")
      (node (ref "P4") (pin "16") (pinfunction "16_16") (pintype "passive"))
    )
    (net (code "186") (name "unconnected-(P4-Pad17)") (class "Default")
      (node (ref "P4") (pin "17") (pinfunction "17_17") (pintype "passive"))
    )
    (net (code "187") (name "unconnected-(P4-Pad18)") (class "Default")
      (node (ref "P4") (pin "18") (pinfunction "18_18") (pintype "passive"))
    )
    (net (code "188") (name "unconnected-(P4-Pad19)") (class "Default")
      (node (ref "P4") (pin "19") (pinfunction "19_19") (pintype "passive"))
    )
    (net (code "189") (name "unconnected-(P4-Pad20)") (class "Default")
      (node (ref "P4") (pin "20") (pinfunction "20_20") (pintype "passive"))
    )
    (net (code "190") (name "unconnected-(P4-Pad24)") (class "Default")
      (node (ref "P4") (pin "24") (pinfunction "24_24") (pintype "passive"))
    )
    (net (code "191") (name "unconnected-(P4-Pad25)") (class "Default")
      (node (ref "P4") (pin "25") (pinfunction "25_25") (pintype "passive"))
    )
    (net (code "192") (name "unconnected-(P4-Pad27)") (class "Default")
      (node (ref "P4") (pin "27") (pinfunction "27_27") (pintype "passive"))
    )
    (net (code "193") (name "unconnected-(PROTECTION-VTSB-Pad15)") (class "Default")
      (node (ref "PROTECTION") (pin "15") (pinfunction "VTSB_15") (pintype "bidirectional"))
    )
    (net (code "194") (name "unconnected-(QG1-E{slash}D-Pad1)") (class "Default")
      (node (ref "QG1") (pin "1") (pinfunction "E/D_1") (pintype "input"))
    )
    (net (code "195") (name "unconnected-(US_2D-S-Pad4)") (class "Default")
      (node (ref "US_2") (pin "4") (pinfunction "S_4") (pintype "passive"))
    )
    (net (code "196") (name "unconnected-(US_4D-S-Pad4)") (class "Default")
      (node (ref "US_4") (pin "4") (pinfunction "S_4") (pintype "passive"))
    )
  )
)
